# adapter_board.net
KiCad netlist of a schematic drawn in EAGLE
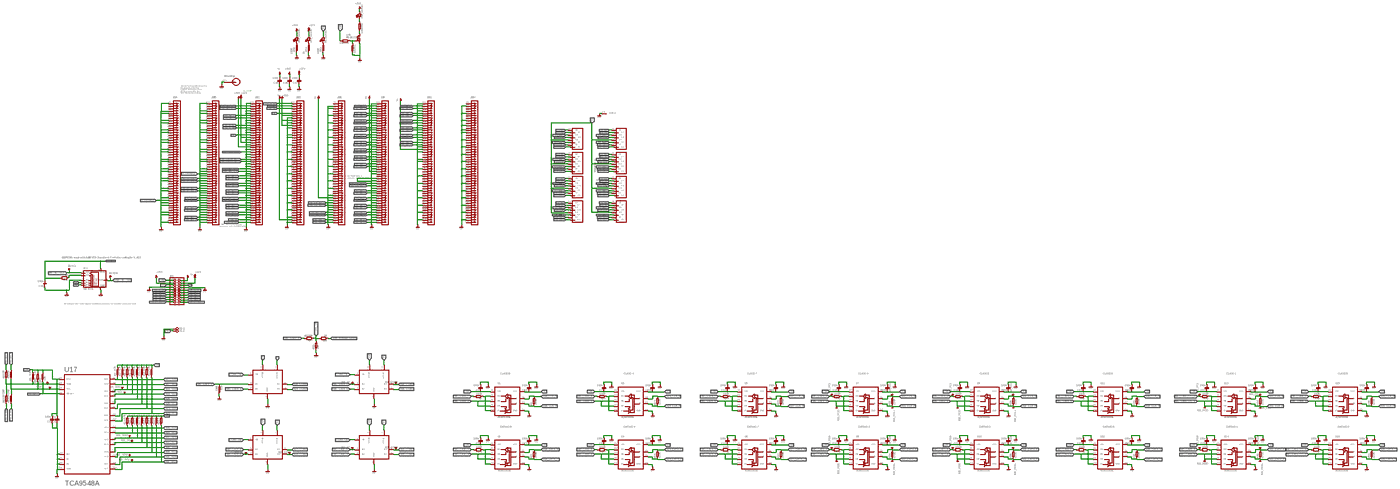
[diagram p0: schematic, sheet 1, overview]
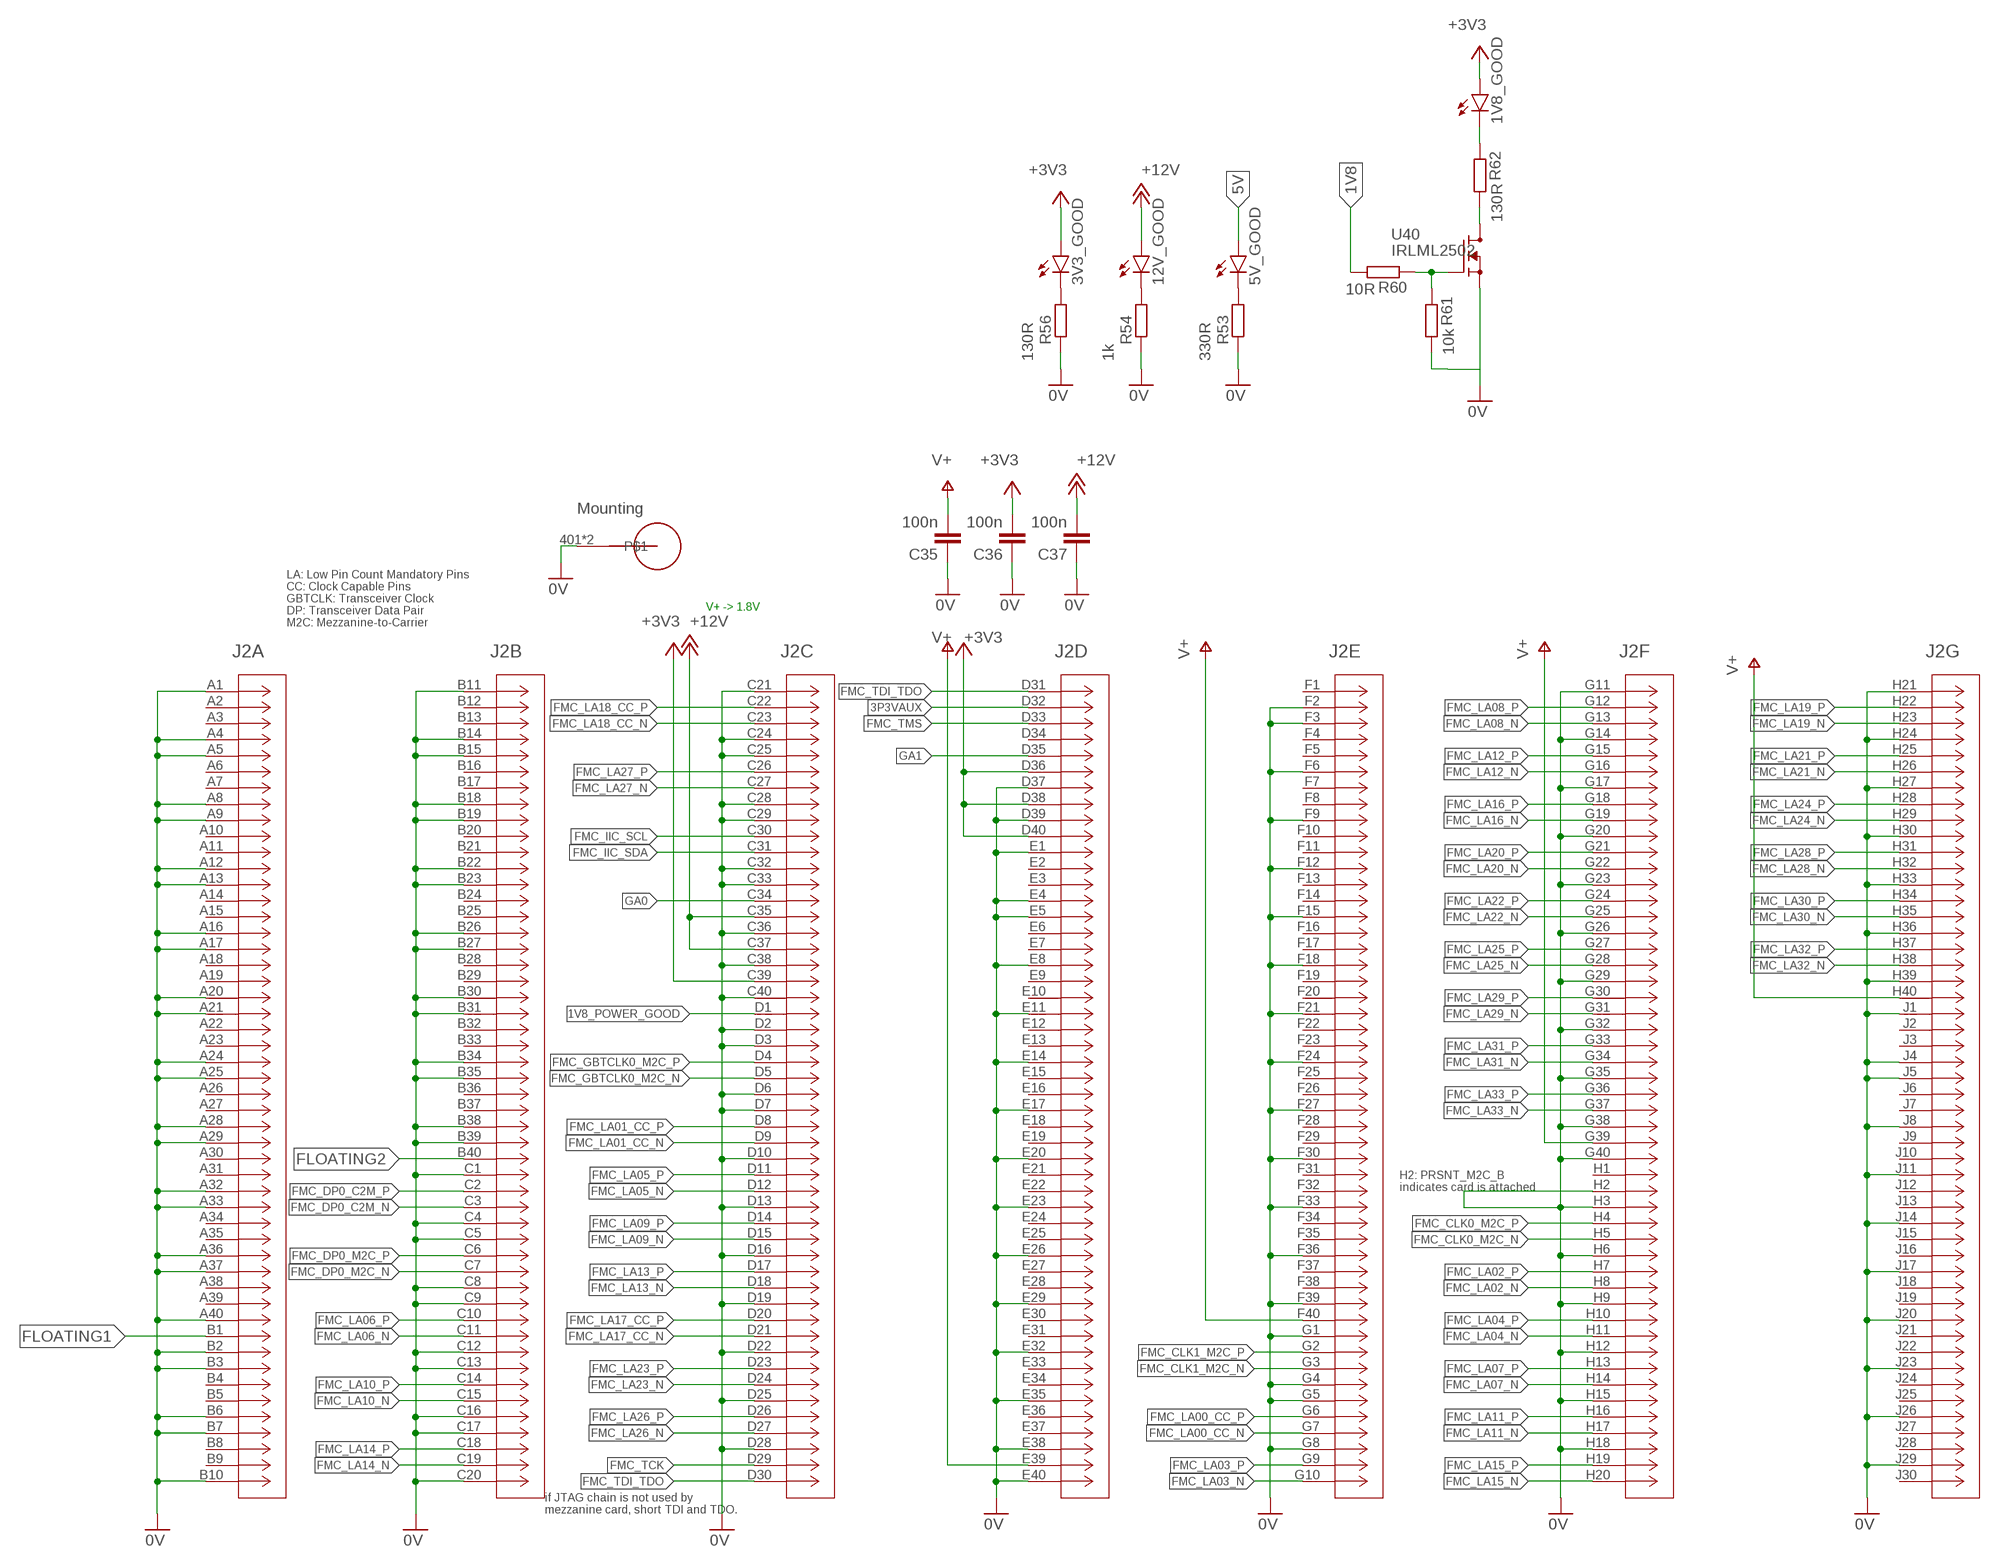
[diagram p1: schematic, sheet 1, part 1 of 5]
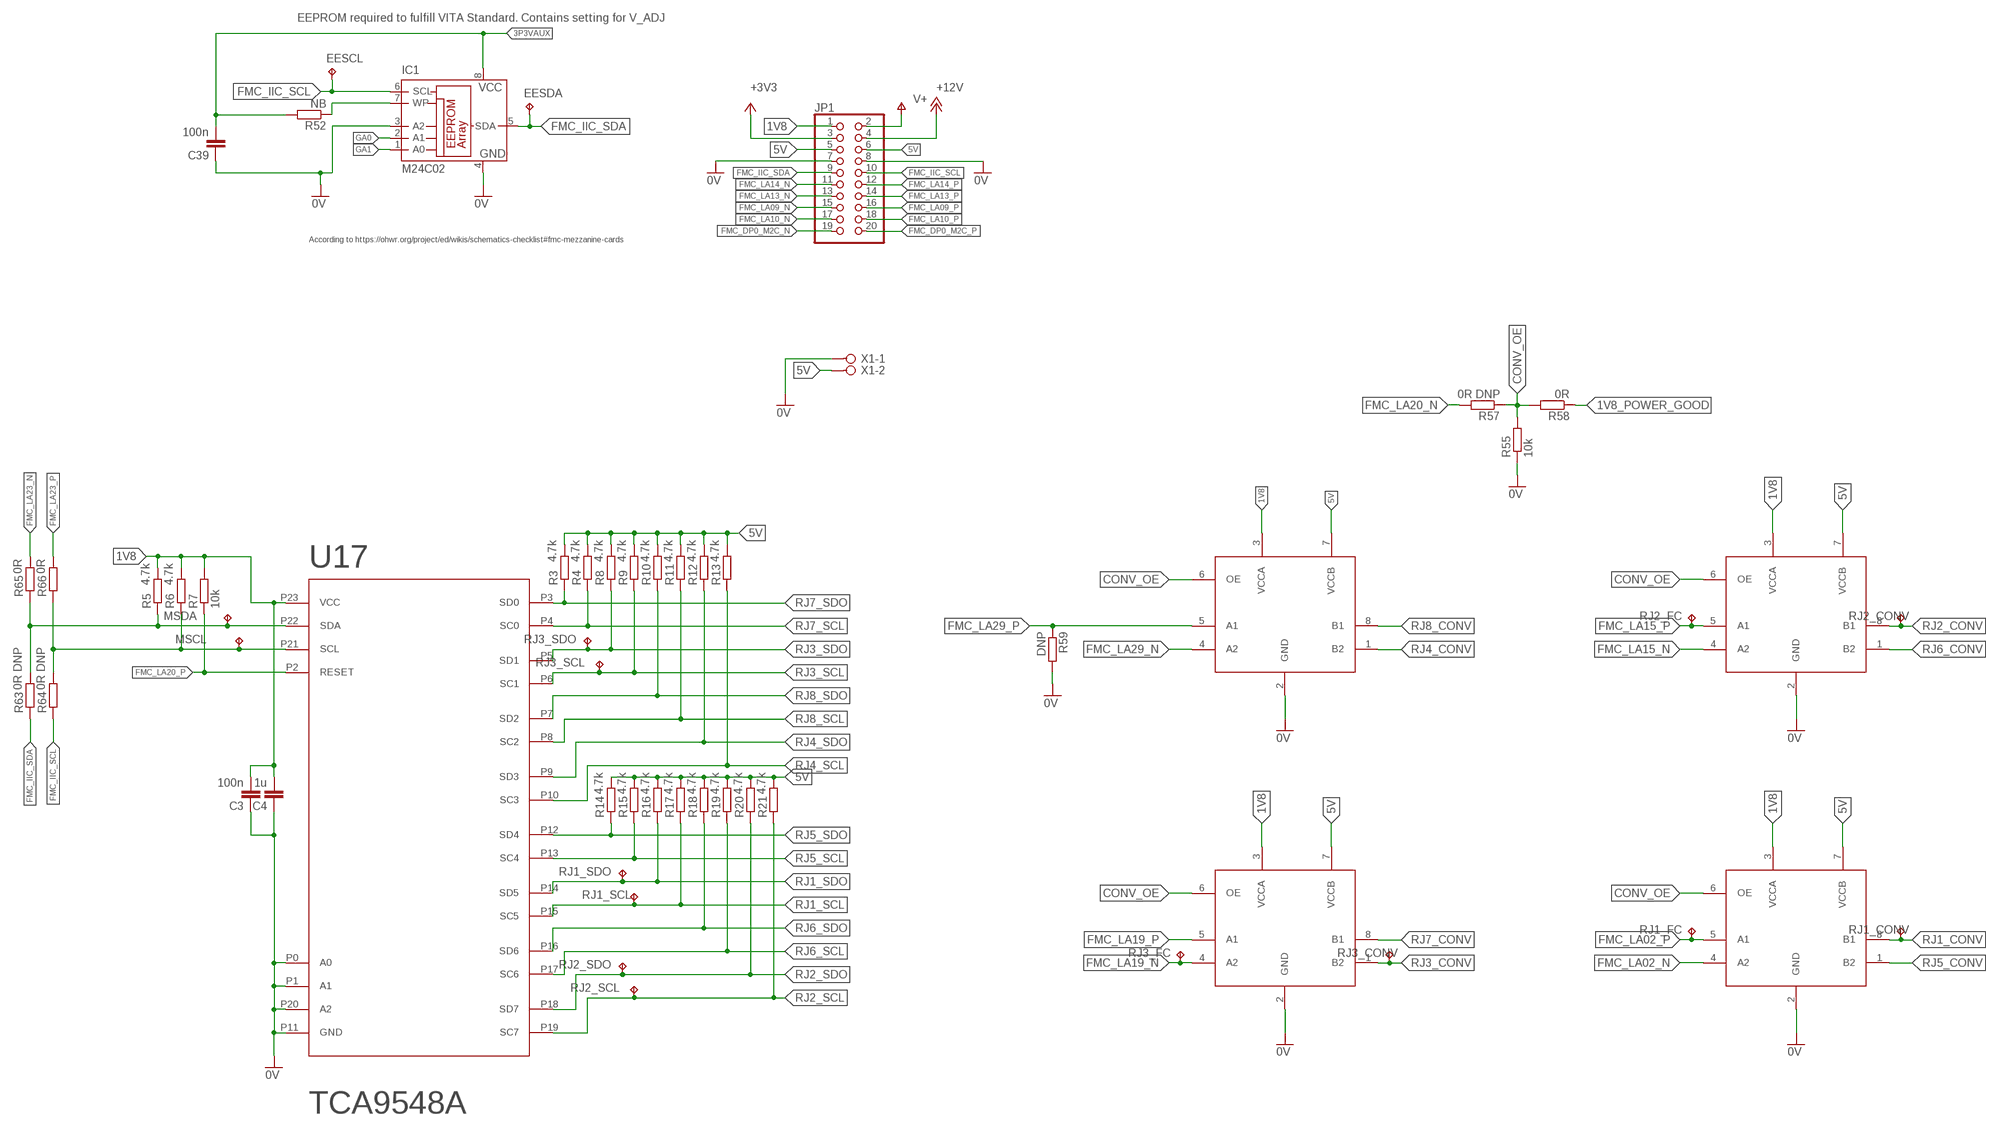
[diagram p2: schematic, sheet 1, part 2 of 5]
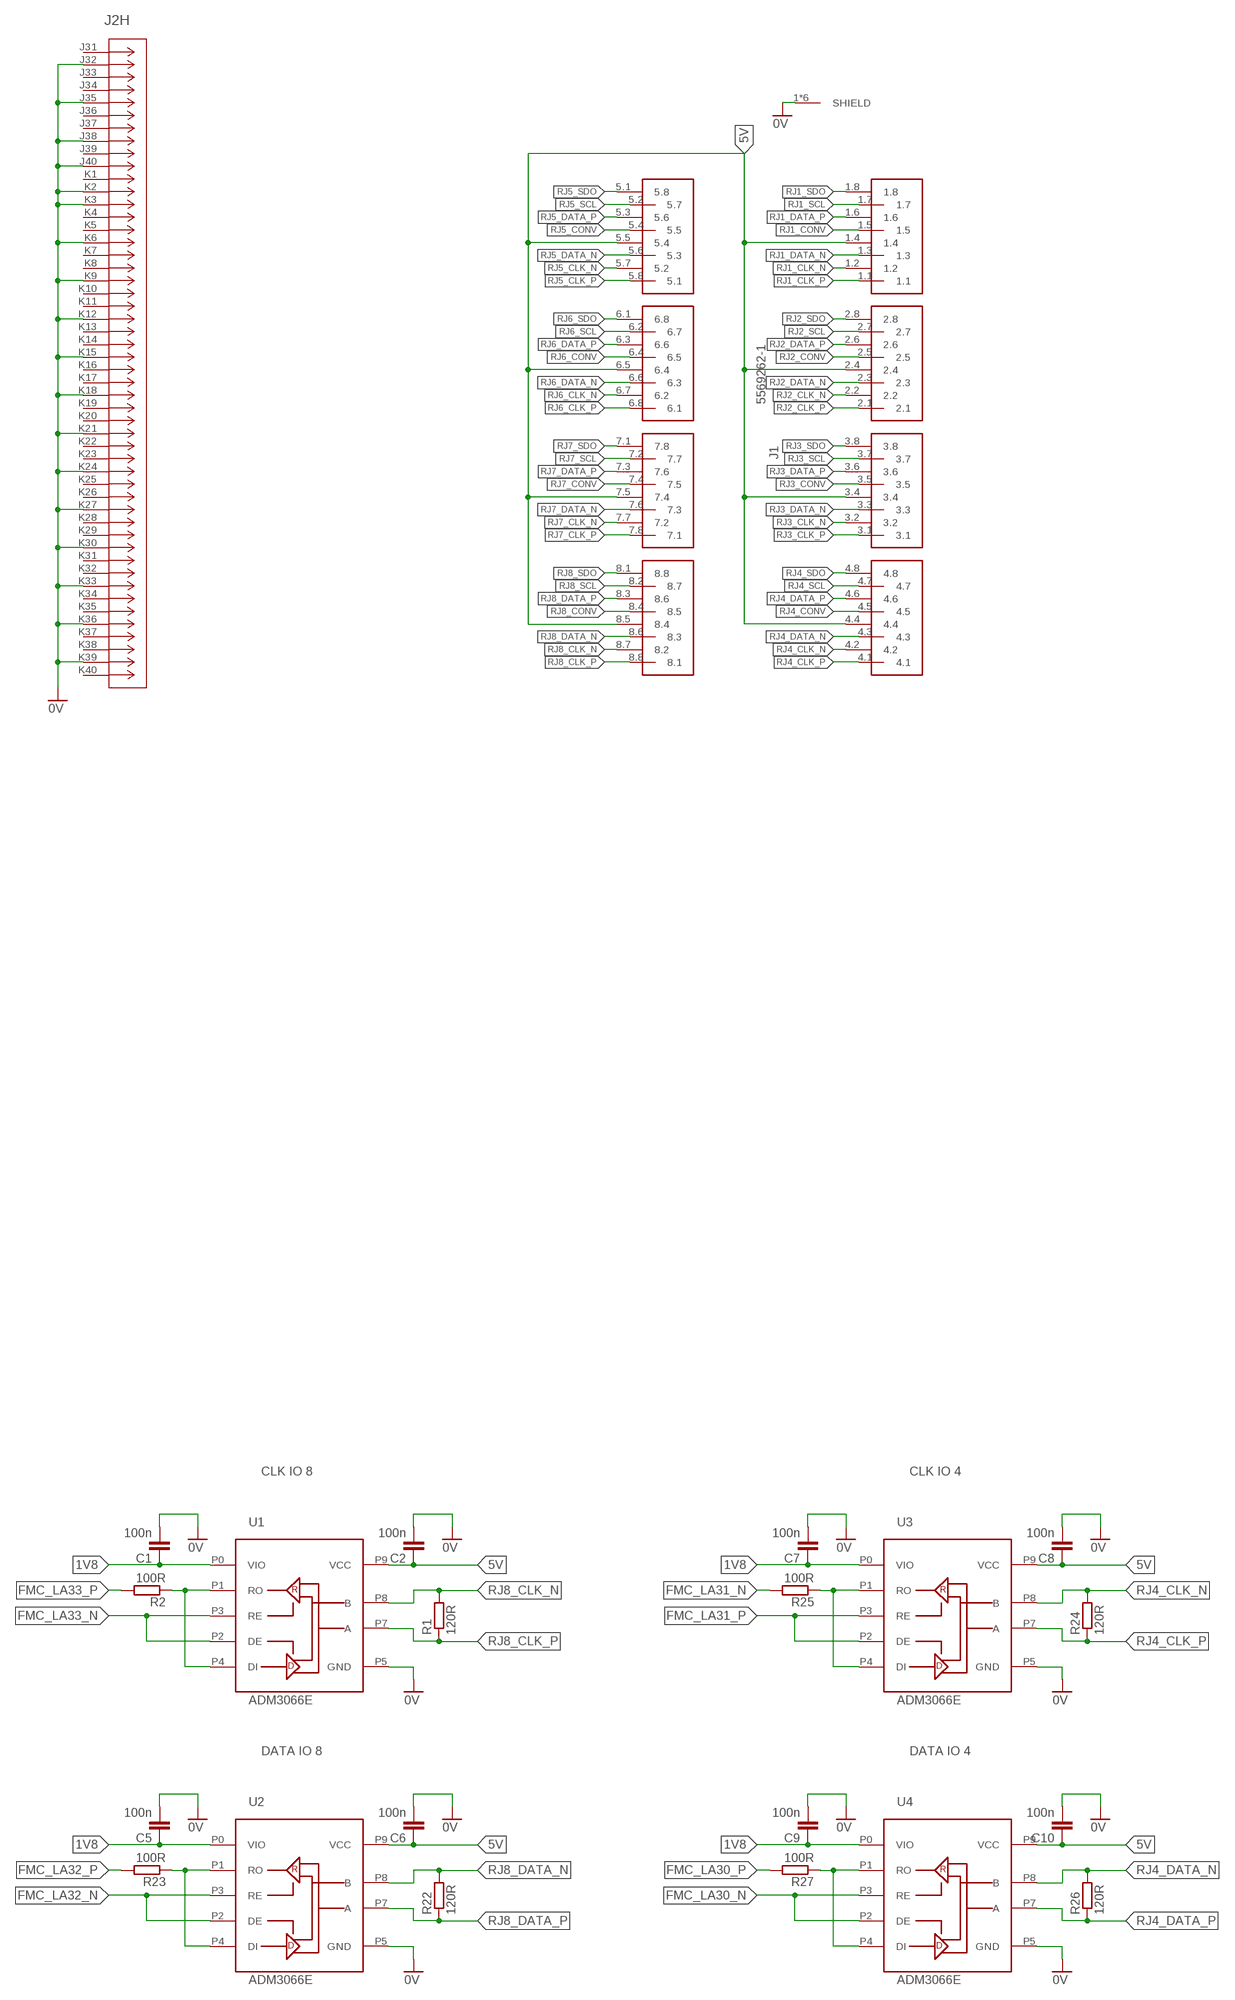
[diagram p3: schematic, sheet 1, part 3 of 5]
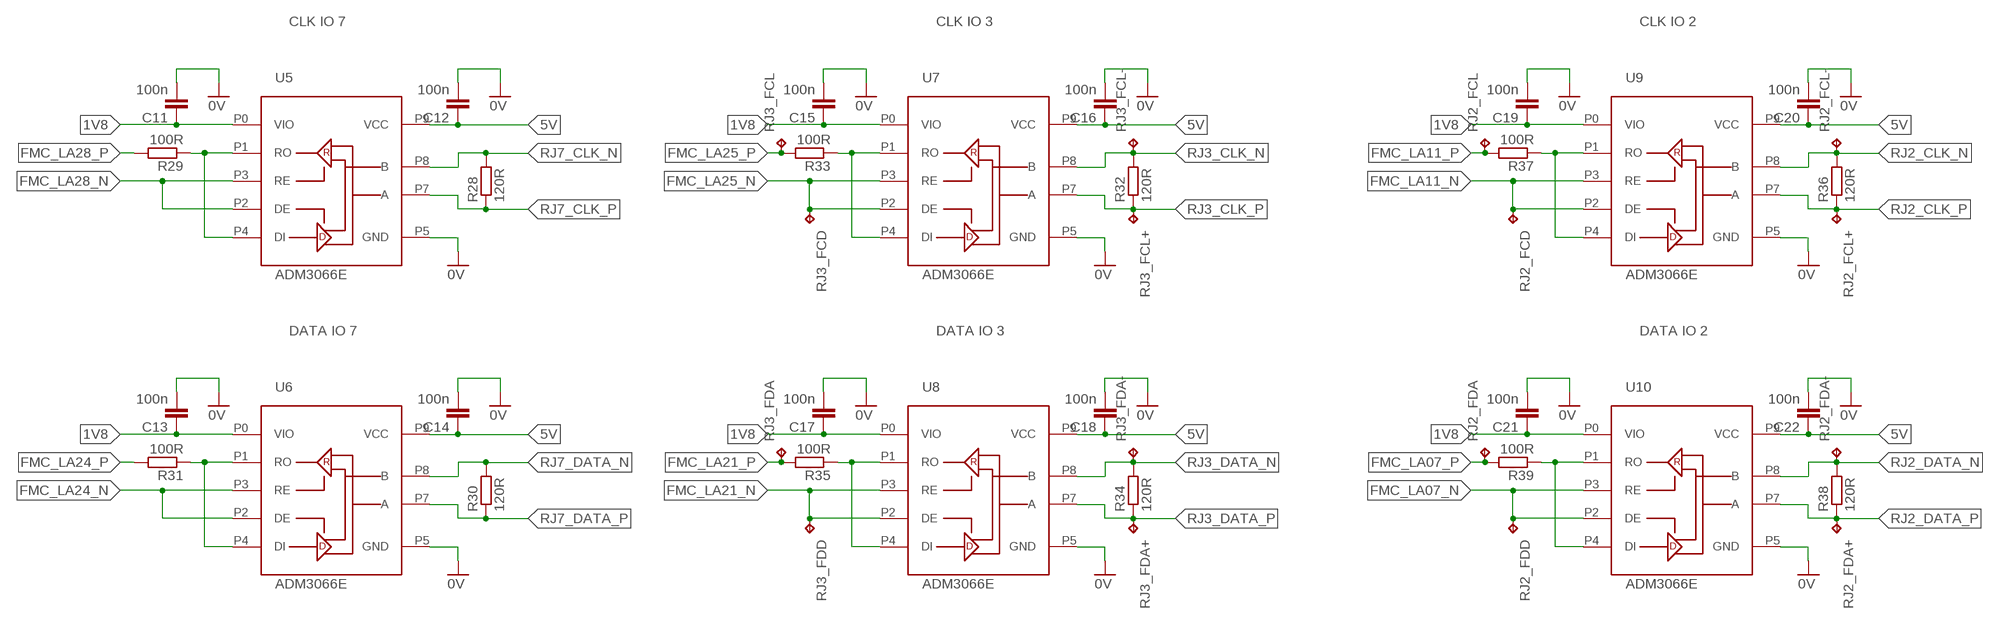
[diagram p4: schematic, sheet 1, part 4 of 5]
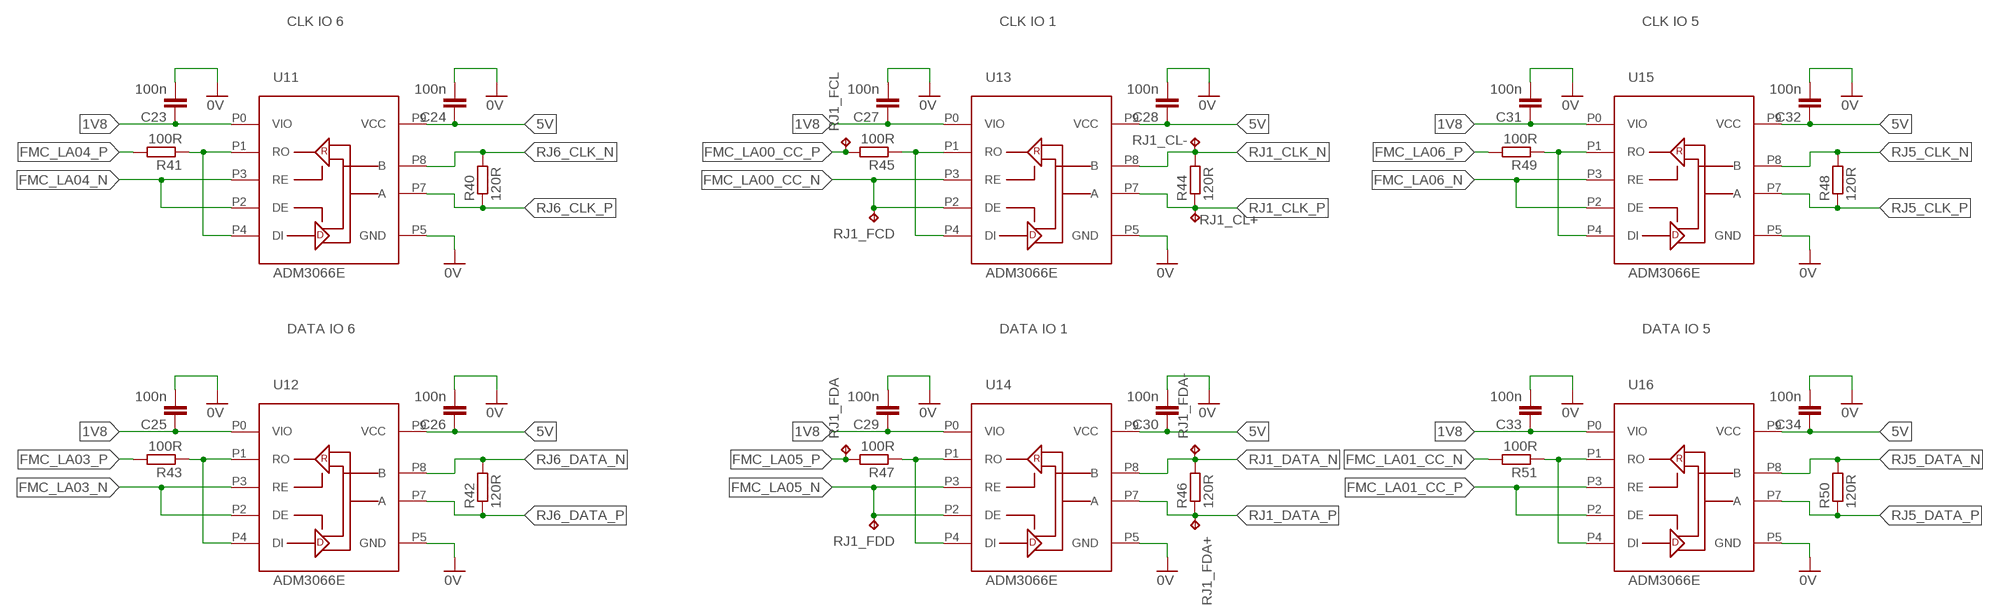
[diagram p5: schematic, sheet 1, part 5 of 5]

(export (version "E")
  (design (tool "Eeschema 10.0.6"))
  (components
    (comp (ref "1V8_GOOD")
      (value "LEDCHIPLED_0805")
      (footprint "eagle-import:CHIPLED_0805")
      (libsource (lib "eagle-import") (part "LEDCHIPLED_0805"))
    )
    (comp (ref "3V3_GOOD")
      (value "LEDCHIPLED_0805")
      (footprint "eagle-import:CHIPLED_0805")
      (libsource (lib "eagle-import") (part "LEDCHIPLED_0805"))
    )
    (comp (ref "5V_GOOD")
      (value "LEDCHIPLED_0805")
      (footprint "eagle-import:CHIPLED_0805")
      (libsource (lib "eagle-import") (part "LEDCHIPLED_0805"))
    )
    (comp (ref "12V_GOOD")
      (value "LEDCHIPLED_0805")
      (footprint "eagle-import:CHIPLED_0805")
      (libsource (lib "eagle-import") (part "LEDCHIPLED_0805"))
    )
    (comp (ref "C1")
      (value "100n")
      (footprint "eagle-import:C0603")
      (libsource (lib "eagle-import") (part "C-EUC0603"))
    )
    (comp (ref "C2")
      (value "100n")
      (footprint "eagle-import:C0603")
      (libsource (lib "eagle-import") (part "C-EUC0603"))
    )
    (comp (ref "C3")
      (value "100n")
      (footprint "eagle-import:C0805")
      (libsource (lib "eagle-import") (part "C-EUC0805"))
    )
    (comp (ref "C4")
      (value "1u")
      (footprint "eagle-import:C0805")
      (libsource (lib "eagle-import") (part "C-EUC0805"))
    )
    (comp (ref "C5")
      (value "100n")
      (footprint "eagle-import:C0603")
      (libsource (lib "eagle-import") (part "C-EUC0603"))
    )
    (comp (ref "C6")
      (value "100n")
      (footprint "eagle-import:C0603")
      (libsource (lib "eagle-import") (part "C-EUC0603"))
    )
    (comp (ref "C7")
      (value "100n")
      (footprint "eagle-import:C0603")
      (libsource (lib "eagle-import") (part "C-EUC0603"))
    )
    (comp (ref "C8")
      (value "100n")
      (footprint "eagle-import:C0603")
      (libsource (lib "eagle-import") (part "C-EUC0603"))
    )
    (comp (ref "C9")
      (value "100n")
      (footprint "eagle-import:C0603")
      (libsource (lib "eagle-import") (part "C-EUC0603"))
    )
    (comp (ref "C10")
      (value "100n")
      (footprint "eagle-import:C0603")
      (libsource (lib "eagle-import") (part "C-EUC0603"))
    )
    (comp (ref "C11")
      (value "100n")
      (footprint "eagle-import:C0603")
      (libsource (lib "eagle-import") (part "C-EUC0603"))
    )
    (comp (ref "C12")
      (value "100n")
      (footprint "eagle-import:C0603")
      (libsource (lib "eagle-import") (part "C-EUC0603"))
    )
    (comp (ref "C13")
      (value "100n")
      (footprint "eagle-import:C0603")
      (libsource (lib "eagle-import") (part "C-EUC0603"))
    )
    (comp (ref "C14")
      (value "100n")
      (footprint "eagle-import:C0603")
      (libsource (lib "eagle-import") (part "C-EUC0603"))
    )
    (comp (ref "C15")
      (value "100n")
      (footprint "eagle-import:C0603")
      (libsource (lib "eagle-import") (part "C-EUC0603"))
    )
    (comp (ref "C16")
      (value "100n")
      (footprint "eagle-import:C0603")
      (libsource (lib "eagle-import") (part "C-EUC0603"))
    )
    (comp (ref "C17")
      (value "100n")
      (footprint "eagle-import:C0603")
      (libsource (lib "eagle-import") (part "C-EUC0603"))
    )
    (comp (ref "C18")
      (value "100n")
      (footprint "eagle-import:C0603")
      (libsource (lib "eagle-import") (part "C-EUC0603"))
    )
    (comp (ref "C19")
      (value "100n")
      (footprint "eagle-import:C0603")
      (libsource (lib "eagle-import") (part "C-EUC0603"))
    )
    (comp (ref "C20")
      (value "100n")
      (footprint "eagle-import:C0603")
      (libsource (lib "eagle-import") (part "C-EUC0603"))
    )
    (comp (ref "C21")
      (value "100n")
      (footprint "eagle-import:C0603")
      (libsource (lib "eagle-import") (part "C-EUC0603"))
    )
    (comp (ref "C22")
      (value "100n")
      (footprint "eagle-import:C0603")
      (libsource (lib "eagle-import") (part "C-EUC0603"))
    )
    (comp (ref "C23")
      (value "100n")
      (footprint "eagle-import:C0603")
      (libsource (lib "eagle-import") (part "C-EUC0603"))
    )
    (comp (ref "C24")
      (value "100n")
      (footprint "eagle-import:C0603")
      (libsource (lib "eagle-import") (part "C-EUC0603"))
    )
    (comp (ref "C25")
      (value "100n")
      (footprint "eagle-import:C0603")
      (libsource (lib "eagle-import") (part "C-EUC0603"))
    )
    (comp (ref "C26")
      (value "100n")
      (footprint "eagle-import:C0603")
      (libsource (lib "eagle-import") (part "C-EUC0603"))
    )
    (comp (ref "C27")
      (value "100n")
      (footprint "eagle-import:C0603")
      (libsource (lib "eagle-import") (part "C-EUC0603"))
    )
    (comp (ref "C28")
      (value "100n")
      (footprint "eagle-import:C0603")
      (libsource (lib "eagle-import") (part "C-EUC0603"))
    )
    (comp (ref "C29")
      (value "100n")
      (footprint "eagle-import:C0603")
      (libsource (lib "eagle-import") (part "C-EUC0603"))
    )
    (comp (ref "C30")
      (value "100n")
      (footprint "eagle-import:C0603")
      (libsource (lib "eagle-import") (part "C-EUC0603"))
    )
    (comp (ref "C31")
      (value "100n")
      (footprint "eagle-import:C0603")
      (libsource (lib "eagle-import") (part "C-EUC0603"))
    )
    (comp (ref "C32")
      (value "100n")
      (footprint "eagle-import:C0603")
      (libsource (lib "eagle-import") (part "C-EUC0603"))
    )
    (comp (ref "C33")
      (value "100n")
      (footprint "eagle-import:C0603")
      (libsource (lib "eagle-import") (part "C-EUC0603"))
    )
    (comp (ref "C34")
      (value "100n")
      (footprint "eagle-import:C0603")
      (libsource (lib "eagle-import") (part "C-EUC0603"))
    )
    (comp (ref "C35")
      (value "100n")
      (footprint "eagle-import:C0603")
      (libsource (lib "eagle-import") (part "C-EUC0603"))
    )
    (comp (ref "C36")
      (value "100n")
      (footprint "eagle-import:C0603")
      (libsource (lib "eagle-import") (part "C-EUC0603"))
    )
    (comp (ref "C37")
      (value "100n")
      (footprint "eagle-import:C0603")
      (libsource (lib "eagle-import") (part "C-EUC0603"))
    )
    (comp (ref "C39")
      (value "100n")
      (footprint "eagle-import:C0603")
      (libsource (lib "eagle-import") (part "C-EUC0603"))
    )
    (comp (ref "EESCL")
      (value "TPB1,27")
      (footprint "eagle-import:B1,27")
      (libsource (lib "eagle-import") (part "TPB1,27"))
    )
    (comp (ref "EESDA")
      (value "TPB1,27")
      (footprint "eagle-import:B1,27")
      (libsource (lib "eagle-import") (part "TPB1,27"))
    )
    (comp (ref "IC1")
      (value "M24C02")
      (footprint "eagle-import:TSSOP-8")
      (libsource (lib "eagle-import") (part "N24C02UDTGTSSOP8"))
    )
    (comp (ref "J1")
      (value "5569262-1")
      (footprint "eagle-import:TE_5569262-1")
      (fields (field (name "MF") "TE Connectivity"))
      (libsource (lib "eagle-import") (part "5569262-1"))
    )
    (comp (ref "J2")
      (value "ASP-134488-01")
      (footprint "eagle-import:CONN_ASP-134488-01_SAI")
      (fields
        (field (name "SPICEPREFIX") "X")
        (field (name "COPYRIGHT") "Copyright (C) 2021 Ultra Librarian. All rights reserved.")
      )
      (libsource (lib "eagle-import") (part "ASP-134488-01"))
    )
    (comp (ref "JP1")
      (value "PINHD-2X10")
      (footprint "eagle-import:2X10")
      (libsource (lib "eagle-import") (part "PINHD-2X10"))
    )
    (comp (ref "MSCL")
      (value "TPB1,27")
      (footprint "eagle-import:B1,27")
      (libsource (lib "eagle-import") (part "TPB1,27"))
    )
    (comp (ref "MSDA")
      (value "TPB1,27")
      (footprint "eagle-import:B1,27")
      (libsource (lib "eagle-import") (part "TPB1,27"))
    )
    (comp (ref "R1")
      (value "120R")
      (footprint "eagle-import:R0805")
      (libsource (lib "eagle-import") (part "R-EU_R0805"))
    )
    (comp (ref "R2")
      (value "100R")
      (footprint "eagle-import:R0603")
      (libsource (lib "eagle-import") (part "R-EU_R0603"))
    )
    (comp (ref "R3")
      (value "4.7k")
      (footprint "eagle-import:R0805")
      (libsource (lib "eagle-import") (part "R-EU_R0805"))
    )
    (comp (ref "R4")
      (value "4.7k")
      (footprint "eagle-import:R0805")
      (libsource (lib "eagle-import") (part "R-EU_R0805"))
    )
    (comp (ref "R5")
      (value "4.7k")
      (footprint "eagle-import:R0603")
      (libsource (lib "eagle-import") (part "R-EU_R0603"))
    )
    (comp (ref "R6")
      (value "4.7k")
      (footprint "eagle-import:R0603")
      (libsource (lib "eagle-import") (part "R-EU_R0603"))
    )
    (comp (ref "R7")
      (value "10k")
      (footprint "eagle-import:R0603")
      (libsource (lib "eagle-import") (part "R-EU_R0603"))
    )
    (comp (ref "R8")
      (value "4.7k")
      (footprint "eagle-import:R0805")
      (libsource (lib "eagle-import") (part "R-EU_R0805"))
    )
    (comp (ref "R9")
      (value "4.7k")
      (footprint "eagle-import:R0805")
      (libsource (lib "eagle-import") (part "R-EU_R0805"))
    )
    (comp (ref "R10")
      (value "4.7k")
      (footprint "eagle-import:R0805")
      (libsource (lib "eagle-import") (part "R-EU_R0805"))
    )
    (comp (ref "R11")
      (value "4.7k")
      (footprint "eagle-import:R0805")
      (libsource (lib "eagle-import") (part "R-EU_R0805"))
    )
    (comp (ref "R12")
      (value "4.7k")
      (footprint "eagle-import:R0805")
      (libsource (lib "eagle-import") (part "R-EU_R0805"))
    )
    (comp (ref "R13")
      (value "4.7k")
      (footprint "eagle-import:R0805")
      (libsource (lib "eagle-import") (part "R-EU_R0805"))
    )
    (comp (ref "R14")
      (value "4.7k")
      (footprint "eagle-import:R0805")
      (libsource (lib "eagle-import") (part "R-EU_R0805"))
    )
    (comp (ref "R15")
      (value "4.7k")
      (footprint "eagle-import:R0805")
      (libsource (lib "eagle-import") (part "R-EU_R0805"))
    )
    (comp (ref "R16")
      (value "4.7k")
      (footprint "eagle-import:R0805")
      (libsource (lib "eagle-import") (part "R-EU_R0805"))
    )
    (comp (ref "R17")
      (value "4.7k")
      (footprint "eagle-import:R0805")
      (libsource (lib "eagle-import") (part "R-EU_R0805"))
    )
    (comp (ref "R18")
      (value "4.7k")
      (footprint "eagle-import:R0805")
      (libsource (lib "eagle-import") (part "R-EU_R0805"))
    )
    (comp (ref "R19")
      (value "4.7k")
      (footprint "eagle-import:R0805")
      (libsource (lib "eagle-import") (part "R-EU_R0805"))
    )
    (comp (ref "R20")
      (value "4.7k")
      (footprint "eagle-import:R0805")
      (libsource (lib "eagle-import") (part "R-EU_R0805"))
    )
    (comp (ref "R21")
      (value "4.7k")
      (footprint "eagle-import:R0805")
      (libsource (lib "eagle-import") (part "R-EU_R0805"))
    )
    (comp (ref "R22")
      (value "120R")
      (footprint "eagle-import:R0805")
      (libsource (lib "eagle-import") (part "R-EU_R0805"))
    )
    (comp (ref "R23")
      (value "100R")
      (footprint "eagle-import:R0603")
      (libsource (lib "eagle-import") (part "R-EU_R0603"))
    )
    (comp (ref "R24")
      (value "120R")
      (footprint "eagle-import:R0805")
      (libsource (lib "eagle-import") (part "R-EU_R0805"))
    )
    (comp (ref "R25")
      (value "100R")
      (footprint "eagle-import:R0603")
      (libsource (lib "eagle-import") (part "R-EU_R0603"))
    )
    (comp (ref "R26")
      (value "120R")
      (footprint "eagle-import:R0805")
      (libsource (lib "eagle-import") (part "R-EU_R0805"))
    )
    (comp (ref "R27")
      (value "100R")
      (footprint "eagle-import:R0603")
      (libsource (lib "eagle-import") (part "R-EU_R0603"))
    )
    (comp (ref "R28")
      (value "120R")
      (footprint "eagle-import:R0805")
      (libsource (lib "eagle-import") (part "R-EU_R0805"))
    )
    (comp (ref "R29")
      (value "100R")
      (footprint "eagle-import:R0603")
      (libsource (lib "eagle-import") (part "R-EU_R0603"))
    )
    (comp (ref "R30")
      (value "120R")
      (footprint "eagle-import:R0805")
      (libsource (lib "eagle-import") (part "R-EU_R0805"))
    )
    (comp (ref "R31")
      (value "100R")
      (footprint "eagle-import:R0603")
      (libsource (lib "eagle-import") (part "R-EU_R0603"))
    )
    (comp (ref "R32")
      (value "120R")
      (footprint "eagle-import:R0805")
      (libsource (lib "eagle-import") (part "R-EU_R0805"))
    )
    (comp (ref "R33")
      (value "100R")
      (footprint "eagle-import:R0603")
      (libsource (lib "eagle-import") (part "R-EU_R0603"))
    )
    (comp (ref "R34")
      (value "120R")
      (footprint "eagle-import:R0805")
      (libsource (lib "eagle-import") (part "R-EU_R0805"))
    )
    (comp (ref "R35")
      (value "100R")
      (footprint "eagle-import:R0603")
      (libsource (lib "eagle-import") (part "R-EU_R0603"))
    )
    (comp (ref "R36")
      (value "120R")
      (footprint "eagle-import:R0805")
      (libsource (lib "eagle-import") (part "R-EU_R0805"))
    )
    (comp (ref "R37")
      (value "100R")
      (footprint "eagle-import:R0603")
      (libsource (lib "eagle-import") (part "R-EU_R0603"))
    )
    (comp (ref "R38")
      (value "120R")
      (footprint "eagle-import:R0805")
      (libsource (lib "eagle-import") (part "R-EU_R0805"))
    )
    (comp (ref "R39")
      (value "100R")
      (footprint "eagle-import:R0603")
      (libsource (lib "eagle-import") (part "R-EU_R0603"))
    )
    (comp (ref "R40")
      (value "120R")
      (footprint "eagle-import:R0805")
      (libsource (lib "eagle-import") (part "R-EU_R0805"))
    )
    (comp (ref "R41")
      (value "100R")
      (footprint "eagle-import:R0603")
      (libsource (lib "eagle-import") (part "R-EU_R0603"))
    )
    (comp (ref "R42")
      (value "120R")
      (footprint "eagle-import:R0805")
      (libsource (lib "eagle-import") (part "R-EU_R0805"))
    )
    (comp (ref "R43")
      (value "100R")
      (footprint "eagle-import:R0603")
      (libsource (lib "eagle-import") (part "R-EU_R0603"))
    )
    (comp (ref "R44")
      (value "120R")
      (footprint "eagle-import:R0805")
      (libsource (lib "eagle-import") (part "R-EU_R0805"))
    )
    (comp (ref "R45")
      (value "100R")
      (footprint "eagle-import:R0603")
      (libsource (lib "eagle-import") (part "R-EU_R0603"))
    )
    (comp (ref "R46")
      (value "120R")
      (footprint "eagle-import:R0805")
      (libsource (lib "eagle-import") (part "R-EU_R0805"))
    )
    (comp (ref "R47")
      (value "100R")
      (footprint "eagle-import:R0603")
      (libsource (lib "eagle-import") (part "R-EU_R0603"))
    )
    (comp (ref "R48")
      (value "120R")
      (footprint "eagle-import:R0805")
      (libsource (lib "eagle-import") (part "R-EU_R0805"))
    )
    (comp (ref "R49")
      (value "100R")
      (footprint "eagle-import:R0603")
      (libsource (lib "eagle-import") (part "R-EU_R0603"))
    )
    (comp (ref "R50")
      (value "120R")
      (footprint "eagle-import:R0805")
      (libsource (lib "eagle-import") (part "R-EU_R0805"))
    )
    (comp (ref "R51")
      (value "100R")
      (footprint "eagle-import:R0603")
      (libsource (lib "eagle-import") (part "R-EU_R0603"))
    )
    (comp (ref "R52")
      (value "NB")
      (footprint "eagle-import:R0603")
      (libsource (lib "eagle-import") (part "R-EU_R0603"))
    )
    (comp (ref "R53")
      (value "330R")
      (footprint "eagle-import:R0805")
      (libsource (lib "eagle-import") (part "resistor_348_R-EU_R0805"))
    )
    (comp (ref "R54")
      (value "1k")
      (footprint "eagle-import:R0805")
      (libsource (lib "eagle-import") (part "resistor_348_R-EU_R0805"))
    )
    (comp (ref "R55")
      (value "10k")
      (footprint "eagle-import:R0603")
      (libsource (lib "eagle-import") (part "R-EU_R0603"))
    )
    (comp (ref "R56")
      (value "130R")
      (footprint "eagle-import:R0805")
      (libsource (lib "eagle-import") (part "resistor_348_R-EU_R0805"))
    )
    (comp (ref "R57")
      (value "0R DNP")
      (footprint "eagle-import:R0603")
      (libsource (lib "eagle-import") (part "R-EU_R0603"))
    )
    (comp (ref "R58")
      (value "0R")
      (footprint "eagle-import:R0603")
      (libsource (lib "eagle-import") (part "R-EU_R0603"))
    )
    (comp (ref "R59")
      (value "DNP")
      (footprint "eagle-import:R0805")
      (libsource (lib "eagle-import") (part "R-EU_R0805"))
    )
    (comp (ref "R60")
      (value "10R")
      (footprint "eagle-import:R0603")
      (libsource (lib "eagle-import") (part "resistor_348_R-EU_R0603"))
    )
    (comp (ref "R61")
      (value "10k")
      (footprint "eagle-import:R0603")
      (libsource (lib "eagle-import") (part "resistor_348_R-EU_R0603"))
    )
    (comp (ref "R62")
      (value "130R")
      (footprint "eagle-import:R0805")
      (libsource (lib "eagle-import") (part "resistor_348_R-EU_R0805"))
    )
    (comp (ref "R63")
      (value "0R DNP")
      (footprint "eagle-import:R0805")
      (libsource (lib "eagle-import") (part "R-EU_R0805"))
    )
    (comp (ref "R64")
      (value "0R DNP")
      (footprint "eagle-import:R0805")
      (libsource (lib "eagle-import") (part "R-EU_R0805"))
    )
    (comp (ref "R65")
      (value "0R")
      (footprint "eagle-import:R0805")
      (libsource (lib "eagle-import") (part "R-EU_R0805"))
    )
    (comp (ref "R66")
      (value "0R")
      (footprint "eagle-import:R0805")
      (libsource (lib "eagle-import") (part "R-EU_R0805"))
    )
    (comp (ref "RJ1_CL+")
      (value "TPB1,27")
      (footprint "eagle-import:B1,27")
      (libsource (lib "eagle-import") (part "TPB1,27"))
    )
    (comp (ref "RJ1_CL-")
      (value "TPB1,27")
      (footprint "eagle-import:B1,27")
      (libsource (lib "eagle-import") (part "TPB1,27"))
    )
    (comp (ref "RJ1_CONV")
      (value "TPB1,27")
      (footprint "eagle-import:B1,27")
      (libsource (lib "eagle-import") (part "TPB1,27"))
    )
    (comp (ref "RJ1_FC")
      (value "TPB1,27")
      (footprint "eagle-import:B1,27")
      (libsource (lib "eagle-import") (part "TPB1,27"))
    )
    (comp (ref "RJ1_FCD")
      (value "TPB1,27")
      (footprint "eagle-import:B1,27")
      (libsource (lib "eagle-import") (part "TPB1,27"))
    )
    (comp (ref "RJ1_FCL")
      (value "TPB1,27")
      (footprint "eagle-import:B1,27")
      (libsource (lib "eagle-import") (part "TPB1,27"))
    )
    (comp (ref "RJ1_FDA")
      (value "TPB1,27")
      (footprint "eagle-import:B1,27")
      (libsource (lib "eagle-import") (part "TPB1,27"))
    )
    (comp (ref "RJ1_FDA+")
      (value "TPB1,27")
      (footprint "eagle-import:B1,27")
      (libsource (lib "eagle-import") (part "TPB1,27"))
    )
    (comp (ref "RJ1_FDA-")
      (value "TPB1,27")
      (footprint "eagle-import:B1,27")
      (libsource (lib "eagle-import") (part "TPB1,27"))
    )
    (comp (ref "RJ1_FDD")
      (value "TPB1,27")
      (footprint "eagle-import:B1,27")
      (libsource (lib "eagle-import") (part "TPB1,27"))
    )
    (comp (ref "RJ1_SCL")
      (value "TPB1,27")
      (footprint "eagle-import:B1,27")
      (libsource (lib "eagle-import") (part "TPB1,27"))
    )
    (comp (ref "RJ1_SDO")
      (value "TPB1,27")
      (footprint "eagle-import:B1,27")
      (libsource (lib "eagle-import") (part "TPB1,27"))
    )
    (comp (ref "RJ2_CONV")
      (value "TPB1,27")
      (footprint "eagle-import:B1,27")
      (libsource (lib "eagle-import") (part "TPB1,27"))
    )
    (comp (ref "RJ2_FC")
      (value "TPB1,27")
      (footprint "eagle-import:B1,27")
      (libsource (lib "eagle-import") (part "TPB1,27"))
    )
    (comp (ref "RJ2_FCD")
      (value "TPB1,27")
      (footprint "eagle-import:B1,27")
      (libsource (lib "eagle-import") (part "TPB1,27"))
    )
    (comp (ref "RJ2_FCL")
      (value "TPB1,27")
      (footprint "eagle-import:B1,27")
      (libsource (lib "eagle-import") (part "TPB1,27"))
    )
    (comp (ref "RJ2_FCL+")
      (value "TPB1,27")
      (footprint "eagle-import:B1,27")
      (libsource (lib "eagle-import") (part "TPB1,27"))
    )
    (comp (ref "RJ2_FCL-")
      (value "TPB1,27")
      (footprint "eagle-import:B1,27")
      (libsource (lib "eagle-import") (part "TPB1,27"))
    )
    (comp (ref "RJ2_FDA")
      (value "TPB1,27")
      (footprint "eagle-import:B1,27")
      (libsource (lib "eagle-import") (part "TPB1,27"))
    )
    (comp (ref "RJ2_FDA+")
      (value "TPB1,27")
      (footprint "eagle-import:B1,27")
      (libsource (lib "eagle-import") (part "TPB1,27"))
    )
    (comp (ref "RJ2_FDA-")
      (value "TPB1,27")
      (footprint "eagle-import:B1,27")
      (libsource (lib "eagle-import") (part "TPB1,27"))
    )
    (comp (ref "RJ2_FDD")
      (value "TPB1,27")
      (footprint "eagle-import:B1,27")
      (libsource (lib "eagle-import") (part "TPB1,27"))
    )
    (comp (ref "RJ2_SCL")
      (value "TPB1,27")
      (footprint "eagle-import:B1,27")
      (libsource (lib "eagle-import") (part "TPB1,27"))
    )
    (comp (ref "RJ2_SDO")
      (value "TPB1,27")
      (footprint "eagle-import:B1,27")
      (libsource (lib "eagle-import") (part "TPB1,27"))
    )
    (comp (ref "RJ3_CONV")
      (value "TPB1,27")
      (footprint "eagle-import:B1,27")
      (libsource (lib "eagle-import") (part "TPB1,27"))
    )
    (comp (ref "RJ3_FC")
      (value "TPB1,27")
      (footprint "eagle-import:B1,27")
      (libsource (lib "eagle-import") (part "TPB1,27"))
    )
    (comp (ref "RJ3_FCD")
      (value "TPB1,27")
      (footprint "eagle-import:B1,27")
      (libsource (lib "eagle-import") (part "TPB1,27"))
    )
    (comp (ref "RJ3_FCL")
      (value "TPB1,27")
      (footprint "eagle-import:B1,27")
      (libsource (lib "eagle-import") (part "TPB1,27"))
    )
    (comp (ref "RJ3_FCL+")
      (value "TPB1,27")
      (footprint "eagle-import:B1,27")
      (libsource (lib "eagle-import") (part "TPB1,27"))
    )
    (comp (ref "RJ3_FCL-")
      (value "TPB1,27")
      (footprint "eagle-import:B1,27")
      (libsource (lib "eagle-import") (part "TPB1,27"))
    )
    (comp (ref "RJ3_FDA")
      (value "TPB1,27")
      (footprint "eagle-import:B1,27")
      (libsource (lib "eagle-import") (part "TPB1,27"))
    )
    (comp (ref "RJ3_FDA+")
      (value "TPB1,27")
      (footprint "eagle-import:B1,27")
      (libsource (lib "eagle-import") (part "TPB1,27"))
    )
    (comp (ref "RJ3_FDA-")
      (value "TPB1,27")
      (footprint "eagle-import:B1,27")
      (libsource (lib "eagle-import") (part "TPB1,27"))
    )
    (comp (ref "RJ3_FDD")
      (value "TPB1,27")
      (footprint "eagle-import:B1,27")
      (libsource (lib "eagle-import") (part "TPB1,27"))
    )
    (comp (ref "RJ3_SCL")
      (value "TPB1,27")
      (footprint "eagle-import:B1,27")
      (libsource (lib "eagle-import") (part "TPB1,27"))
    )
    (comp (ref "RJ3_SDO")
      (value "TPB1,27")
      (footprint "eagle-import:B1,27")
      (libsource (lib "eagle-import") (part "TPB1,27"))
    )
    (comp (ref "U1")
      (value "ADM3066E")
      (footprint "eagle-import:MSOP-10")
      (libsource (lib "eagle-import") (part "ADM3066E"))
    )
    (comp (ref "U2")
      (value "ADM3066E")
      (footprint "eagle-import:MSOP-10")
      (libsource (lib "eagle-import") (part "ADM3066E"))
    )
    (comp (ref "U3")
      (value "ADM3066E")
      (footprint "eagle-import:MSOP-10")
      (libsource (lib "eagle-import") (part "ADM3066E"))
    )
    (comp (ref "U4")
      (value "ADM3066E")
      (footprint "eagle-import:MSOP-10")
      (libsource (lib "eagle-import") (part "ADM3066E"))
    )
    (comp (ref "U5")
      (value "ADM3066E")
      (footprint "eagle-import:MSOP-10")
      (libsource (lib "eagle-import") (part "ADM3066E"))
    )
    (comp (ref "U6")
      (value "ADM3066E")
      (footprint "eagle-import:MSOP-10")
      (libsource (lib "eagle-import") (part "ADM3066E"))
    )
    (comp (ref "U7")
      (value "ADM3066E")
      (footprint "eagle-import:MSOP-10")
      (libsource (lib "eagle-import") (part "ADM3066E"))
    )
    (comp (ref "U8")
      (value "ADM3066E")
      (footprint "eagle-import:MSOP-10")
      (libsource (lib "eagle-import") (part "ADM3066E"))
    )
    (comp (ref "U9")
      (value "ADM3066E")
      (footprint "eagle-import:MSOP-10")
      (libsource (lib "eagle-import") (part "ADM3066E"))
    )
    (comp (ref "U10")
      (value "ADM3066E")
      (footprint "eagle-import:MSOP-10")
      (libsource (lib "eagle-import") (part "ADM3066E"))
    )
    (comp (ref "U11")
      (value "ADM3066E")
      (footprint "eagle-import:MSOP-10")
      (libsource (lib "eagle-import") (part "ADM3066E"))
    )
    (comp (ref "U12")
      (value "ADM3066E")
      (footprint "eagle-import:MSOP-10")
      (libsource (lib "eagle-import") (part "ADM3066E"))
    )
    (comp (ref "U13")
      (value "ADM3066E")
      (footprint "eagle-import:MSOP-10")
      (libsource (lib "eagle-import") (part "ADM3066E"))
    )
    (comp (ref "U14")
      (value "ADM3066E")
      (footprint "eagle-import:MSOP-10")
      (libsource (lib "eagle-import") (part "ADM3066E"))
    )
    (comp (ref "U15")
      (value "ADM3066E")
      (footprint "eagle-import:MSOP-10")
      (libsource (lib "eagle-import") (part "ADM3066E"))
    )
    (comp (ref "U16")
      (value "ADM3066E")
      (footprint "eagle-import:MSOP-10")
      (libsource (lib "eagle-import") (part "ADM3066E"))
    )
    (comp (ref "U17")
      (value "TCA9548A")
      (footprint "eagle-import:PCA9548")
      (libsource (lib "eagle-import") (part "PCA9548A"))
    )
    (comp (ref "U18")
      (value "TXS0102")
      (footprint "eagle-import:VSSOP-8")
      (libsource (lib "eagle-import") (part "TXS0102"))
    )
    (comp (ref "U19")
      (value "TXS0102")
      (footprint "eagle-import:VSSOP-8")
      (libsource (lib "eagle-import") (part "TXS0102"))
    )
    (comp (ref "U20")
      (value "TXS0102")
      (footprint "eagle-import:VSSOP-8")
      (libsource (lib "eagle-import") (part "TXS0102"))
    )
    (comp (ref "U21")
      (value "TXS0102")
      (footprint "eagle-import:VSSOP-8")
      (libsource (lib "eagle-import") (part "TXS0102"))
    )
    (comp (ref "U40")
      (value "IRLML2502")
      (footprint "eagle-import:SOT23-IRLML")
      (libsource (lib "eagle-import") (part "IRLML2502"))
    )
    (comp (ref "X1")
      (value "W237-02P")
      (footprint "eagle-import:W237-132")
      (libsource (lib "eagle-import") (part "W237-02P"))
    )
  )
  (nets
    (net (code "1") (name "+3V3") (class "Default")
      (node (ref "1V8_GOOD") (pin "A") (pinfunction "A_A") (pintype "passive"))
      (node (ref "3V3_GOOD") (pin "A") (pinfunction "A_A") (pintype "passive"))
      (node (ref "C36") (pin "2") (pinfunction "2_2") (pintype "passive"))
      (node (ref "J2") (pin "C39") (pinfunction "C39_C39") (pintype "passive"))
      (node (ref "J2") (pin "D36") (pinfunction "D36_D36") (pintype "passive"))
      (node (ref "J2") (pin "D38") (pinfunction "D38_D38") (pintype "passive"))
      (node (ref "J2") (pin "D40") (pinfunction "D40_D40") (pintype "passive"))
      (node (ref "JP1") (pin "3") (pinfunction "3_3") (pintype "passive"))
    )
    (net (code "2") (name "+12V") (class "Default")
      (node (ref "12V_GOOD") (pin "A") (pinfunction "A_A") (pintype "passive"))
      (node (ref "C37") (pin "2") (pinfunction "2_2") (pintype "passive"))
      (node (ref "J2") (pin "C35") (pinfunction "C35_C35") (pintype "passive"))
      (node (ref "J2") (pin "C37") (pinfunction "C37_C37") (pintype "passive"))
      (node (ref "JP1") (pin "4") (pinfunction "4_4") (pintype "passive"))
    )
    (net (code "3") (name "0V") (class "Default")
      (node (ref "C1") (pin "2") (pinfunction "2_2") (pintype "passive"))
      (node (ref "C10") (pin "2") (pinfunction "2_2") (pintype "passive"))
      (node (ref "C11") (pin "2") (pinfunction "2_2") (pintype "passive"))
      (node (ref "C12") (pin "2") (pinfunction "2_2") (pintype "passive"))
      (node (ref "C13") (pin "2") (pinfunction "2_2") (pintype "passive"))
      (node (ref "C14") (pin "2") (pinfunction "2_2") (pintype "passive"))
      (node (ref "C15") (pin "2") (pinfunction "2_2") (pintype "passive"))
      (node (ref "C16") (pin "2") (pinfunction "2_2") (pintype "passive"))
      (node (ref "C17") (pin "2") (pinfunction "2_2") (pintype "passive"))
      (node (ref "C18") (pin "2") (pinfunction "2_2") (pintype "passive"))
      (node (ref "C19") (pin "2") (pinfunction "2_2") (pintype "passive"))
      (node (ref "C2") (pin "2") (pinfunction "2_2") (pintype "passive"))
      (node (ref "C20") (pin "2") (pinfunction "2_2") (pintype "passive"))
      (node (ref "C21") (pin "2") (pinfunction "2_2") (pintype "passive"))
      (node (ref "C22") (pin "2") (pinfunction "2_2") (pintype "passive"))
      (node (ref "C23") (pin "2") (pinfunction "2_2") (pintype "passive"))
      (node (ref "C24") (pin "2") (pinfunction "2_2") (pintype "passive"))
      (node (ref "C25") (pin "2") (pinfunction "2_2") (pintype "passive"))
      (node (ref "C26") (pin "2") (pinfunction "2_2") (pintype "passive"))
      (node (ref "C27") (pin "2") (pinfunction "2_2") (pintype "passive"))
      (node (ref "C28") (pin "2") (pinfunction "2_2") (pintype "passive"))
      (node (ref "C29") (pin "2") (pinfunction "2_2") (pintype "passive"))
      (node (ref "C3") (pin "1") (pinfunction "1_1") (pintype "passive"))
      (node (ref "C30") (pin "2") (pinfunction "2_2") (pintype "passive"))
      (node (ref "C31") (pin "2") (pinfunction "2_2") (pintype "passive"))
      (node (ref "C32") (pin "2") (pinfunction "2_2") (pintype "passive"))
      (node (ref "C33") (pin "2") (pinfunction "2_2") (pintype "passive"))
      (node (ref "C34") (pin "2") (pinfunction "2_2") (pintype "passive"))
      (node (ref "C35") (pin "1") (pinfunction "1_1") (pintype "passive"))
      (node (ref "C36") (pin "1") (pinfunction "1_1") (pintype "passive"))
      (node (ref "C37") (pin "1") (pinfunction "1_1") (pintype "passive"))
      (node (ref "C39") (pin "1") (pinfunction "1_1") (pintype "passive"))
      (node (ref "C4") (pin "1") (pinfunction "1_1") (pintype "passive"))
      (node (ref "C5") (pin "2") (pinfunction "2_2") (pintype "passive"))
      (node (ref "C6") (pin "2") (pinfunction "2_2") (pintype "passive"))
      (node (ref "C7") (pin "2") (pinfunction "2_2") (pintype "passive"))
      (node (ref "C8") (pin "2") (pinfunction "2_2") (pintype "passive"))
      (node (ref "C9") (pin "2") (pinfunction "2_2") (pintype "passive"))
      (node (ref "IC1") (pin "3") (pinfunction "A2_3") (pintype "input"))
      (node (ref "IC1") (pin "4") (pinfunction "GND_4") (pintype "power_in"))
      (node (ref "J1") (pin "1") (pinfunction "SHIELD_1") (pintype "bidirectional"))
      (node (ref "J1") (pin "2") (pinfunction "SHIELD_2") (pintype "bidirectional"))
      (node (ref "J1") (pin "3") (pinfunction "SHIELD_3") (pintype "bidirectional"))
      (node (ref "J1") (pin "4") (pinfunction "SHIELD_4") (pintype "bidirectional"))
      (node (ref "J1") (pin "5") (pinfunction "SHIELD_5") (pintype "bidirectional"))
      (node (ref "J1") (pin "6") (pinfunction "SHIELD_6") (pintype "bidirectional"))
      (node (ref "J2") (pin "401") (pinfunction "P$1_401") (pintype "bidirectional"))
      (node (ref "J2") (pin "402") (pinfunction "P$1_402") (pintype "bidirectional"))
      (node (ref "J2") (pin "A1") (pinfunction "A1_A1") (pintype "passive"))
      (node (ref "J2") (pin "A12") (pinfunction "A12_A12") (pintype "passive"))
      (node (ref "J2") (pin "A13") (pinfunction "A13_A13") (pintype "passive"))
      (node (ref "J2") (pin "A16") (pinfunction "A16_A16") (pintype "passive"))
      (node (ref "J2") (pin "A17") (pinfunction "A17_A17") (pintype "passive"))
      (node (ref "J2") (pin "A20") (pinfunction "A20_A20") (pintype "passive"))
      (node (ref "J2") (pin "A21") (pinfunction "A21_A21") (pintype "passive"))
      (node (ref "J2") (pin "A24") (pinfunction "A24_A24") (pintype "passive"))
      (node (ref "J2") (pin "A25") (pinfunction "A25_A25") (pintype "passive"))
      (node (ref "J2") (pin "A28") (pinfunction "A28_A28") (pintype "passive"))
      (node (ref "J2") (pin "A29") (pinfunction "A29_A29") (pintype "passive"))
      (node (ref "J2") (pin "A32") (pinfunction "A32_A32") (pintype "passive"))
      (node (ref "J2") (pin "A33") (pinfunction "A33_A33") (pintype "passive"))
      (node (ref "J2") (pin "A36") (pinfunction "A36_A36") (pintype "passive"))
      (node (ref "J2") (pin "A37") (pinfunction "A37_A37") (pintype "passive"))
      (node (ref "J2") (pin "A4") (pinfunction "A4_A4") (pintype "passive"))
      (node (ref "J2") (pin "A40") (pinfunction "A40_A40") (pintype "passive"))
      (node (ref "J2") (pin "A5") (pinfunction "A5_A5") (pintype "passive"))
      (node (ref "J2") (pin "A8") (pinfunction "A8_A8") (pintype "passive"))
      (node (ref "J2") (pin "A9") (pinfunction "A9_A9") (pintype "passive"))
      (node (ref "J2") (pin "B10") (pinfunction "B10_B10") (pintype "passive"))
      (node (ref "J2") (pin "B11") (pinfunction "B11_B11") (pintype "passive"))
      (node (ref "J2") (pin "B14") (pinfunction "B14_B14") (pintype "passive"))
      (node (ref "J2") (pin "B15") (pinfunction "B15_B15") (pintype "passive"))
      (node (ref "J2") (pin "B18") (pinfunction "B18_B18") (pintype "passive"))
      (node (ref "J2") (pin "B19") (pinfunction "B19_B19") (pintype "passive"))
      (node (ref "J2") (pin "B2") (pinfunction "B2_B2") (pintype "passive"))
      (node (ref "J2") (pin "B22") (pinfunction "B22_B22") (pintype "passive"))
      (node (ref "J2") (pin "B23") (pinfunction "B23_B23") (pintype "passive"))
      (node (ref "J2") (pin "B26") (pinfunction "B26_B26") (pintype "passive"))
      (node (ref "J2") (pin "B27") (pinfunction "B27_B27") (pintype "passive"))
      (node (ref "J2") (pin "B3") (pinfunction "B3_B3") (pintype "passive"))
      (node (ref "J2") (pin "B30") (pinfunction "B30_B30") (pintype "passive"))
      (node (ref "J2") (pin "B31") (pinfunction "B31_B31") (pintype "passive"))
      (node (ref "J2") (pin "B34") (pinfunction "B34_B34") (pintype "passive"))
      (node (ref "J2") (pin "B35") (pinfunction "B35_B35") (pintype "passive"))
      (node (ref "J2") (pin "B38") (pinfunction "B38_B38") (pintype "passive"))
      (node (ref "J2") (pin "B39") (pinfunction "B39_B39") (pintype "passive"))
      (node (ref "J2") (pin "B6") (pinfunction "B6_B6") (pintype "passive"))
      (node (ref "J2") (pin "B7") (pinfunction "B7_B7") (pintype "passive"))
      (node (ref "J2") (pin "C1") (pinfunction "C1_C1") (pintype "passive"))
      (node (ref "J2") (pin "C12") (pinfunction "C12_C12") (pintype "passive"))
      (node (ref "J2") (pin "C13") (pinfunction "C13_C13") (pintype "passive"))
      (node (ref "J2") (pin "C16") (pinfunction "C16_C16") (pintype "passive"))
      (node (ref "J2") (pin "C17") (pinfunction "C17_C17") (pintype "passive"))
      (node (ref "J2") (pin "C20") (pinfunction "C20_C20") (pintype "passive"))
      (node (ref "J2") (pin "C21") (pinfunction "C21_C21") (pintype "passive"))
      (node (ref "J2") (pin "C24") (pinfunction "C24_C24") (pintype "passive"))
      (node (ref "J2") (pin "C25") (pinfunction "C25_C25") (pintype "passive"))
      (node (ref "J2") (pin "C28") (pinfunction "C28_C28") (pintype "passive"))
      (node (ref "J2") (pin "C29") (pinfunction "C29_C29") (pintype "passive"))
      (node (ref "J2") (pin "C32") (pinfunction "C32_C32") (pintype "passive"))
      (node (ref "J2") (pin "C33") (pinfunction "C33_C33") (pintype "passive"))
      (node (ref "J2") (pin "C36") (pinfunction "C36_C36") (pintype "passive"))
      (node (ref "J2") (pin "C38") (pinfunction "C38_C38") (pintype "passive"))
      (node (ref "J2") (pin "C4") (pinfunction "C4_C4") (pintype "passive"))
      (node (ref "J2") (pin "C40") (pinfunction "C40_C40") (pintype "passive"))
      (node (ref "J2") (pin "C5") (pinfunction "C5_C5") (pintype "passive"))
      (node (ref "J2") (pin "C8") (pinfunction "C8_C8") (pintype "passive"))
      (node (ref "J2") (pin "C9") (pinfunction "C9_C9") (pintype "passive"))
      (node (ref "J2") (pin "D10") (pinfunction "D10_D10") (pintype "passive"))
      (node (ref "J2") (pin "D13") (pinfunction "D13_D13") (pintype "passive"))
      (node (ref "J2") (pin "D16") (pinfunction "D16_D16") (pintype "passive"))
      (node (ref "J2") (pin "D19") (pinfunction "D19_D19") (pintype "passive"))
      (node (ref "J2") (pin "D2") (pinfunction "D2_D2") (pintype "passive"))
      (node (ref "J2") (pin "D22") (pinfunction "D22_D22") (pintype "passive"))
      (node (ref "J2") (pin "D25") (pinfunction "D25_D25") (pintype "passive"))
      (node (ref "J2") (pin "D28") (pinfunction "D28_D28") (pintype "passive"))
      (node (ref "J2") (pin "D3") (pinfunction "D3_D3") (pintype "passive"))
      (node (ref "J2") (pin "D37") (pinfunction "D37_D37") (pintype "passive"))
      (node (ref "J2") (pin "D39") (pinfunction "D39_D39") (pintype "passive"))
      (node (ref "J2") (pin "D6") (pinfunction "D6_D6") (pintype "passive"))
      (node (ref "J2") (pin "D7") (pinfunction "D7_D7") (pintype "passive"))
      (node (ref "J2") (pin "E1") (pinfunction "E1_E1") (pintype "passive"))
      (node (ref "J2") (pin "E11") (pinfunction "E11_E11") (pintype "passive"))
      (node (ref "J2") (pin "E14") (pinfunction "E14_E14") (pintype "passive"))
      (node (ref "J2") (pin "E17") (pinfunction "E17_E17") (pintype "passive"))
      (node (ref "J2") (pin "E20") (pinfunction "E20_E20") (pintype "passive"))
      (node (ref "J2") (pin "E23") (pinfunction "E23_E23") (pintype "passive"))
      (node (ref "J2") (pin "E26") (pinfunction "E26_E26") (pintype "passive"))
      (node (ref "J2") (pin "E29") (pinfunction "E29_E29") (pintype "passive"))
      (node (ref "J2") (pin "E32") (pinfunction "E32_E32") (pintype "passive"))
      (node (ref "J2") (pin "E35") (pinfunction "E35_E35") (pintype "passive"))
      (node (ref "J2") (pin "E38") (pinfunction "E38_E38") (pintype "passive"))
      (node (ref "J2") (pin "E4") (pinfunction "E4_E4") (pintype "passive"))
      (node (ref "J2") (pin "E40") (pinfunction "E40_E40") (pintype "passive"))
      (node (ref "J2") (pin "E5") (pinfunction "E5_E5") (pintype "passive"))
      (node (ref "J2") (pin "E8") (pinfunction "E8_E8") (pintype "passive"))
      (node (ref "J2") (pin "F12") (pinfunction "F12_F12") (pintype "passive"))
      (node (ref "J2") (pin "F15") (pinfunction "F15_F15") (pintype "passive"))
      (node (ref "J2") (pin "F18") (pinfunction "F18_F18") (pintype "passive"))
      (node (ref "J2") (pin "F2") (pinfunction "F2_F2") (pintype "passive"))
      (node (ref "J2") (pin "F21") (pinfunction "F21_F21") (pintype "passive"))
      (node (ref "J2") (pin "F24") (pinfunction "F24_F24") (pintype "passive"))
      (node (ref "J2") (pin "F27") (pinfunction "F27_F27") (pintype "passive"))
      (node (ref "J2") (pin "F3") (pinfunction "F3_F3") (pintype "passive"))
      (node (ref "J2") (pin "F30") (pinfunction "F30_F30") (pintype "passive"))
      (node (ref "J2") (pin "F33") (pinfunction "F33_F33") (pintype "passive"))
      (node (ref "J2") (pin "F36") (pinfunction "F36_F36") (pintype "passive"))
      (node (ref "J2") (pin "F39") (pinfunction "F39_F39") (pintype "passive"))
      (node (ref "J2") (pin "F6") (pinfunction "F6_F6") (pintype "passive"))
      (node (ref "J2") (pin "F9") (pinfunction "F9_F9") (pintype "passive"))
      (node (ref "J2") (pin "G1") (pinfunction "G1_G1") (pintype "passive"))
      (node (ref "J2") (pin "G11") (pinfunction "G11_G11") (pintype "passive"))
      (node (ref "J2") (pin "G14") (pinfunction "G14_G14") (pintype "passive"))
      (node (ref "J2") (pin "G17") (pinfunction "G17_G17") (pintype "passive"))
      (node (ref "J2") (pin "G20") (pinfunction "G20_G20") (pintype "passive"))
      (node (ref "J2") (pin "G23") (pinfunction "G23_G23") (pintype "passive"))
      (node (ref "J2") (pin "G26") (pinfunction "G26_G26") (pintype "passive"))
      (node (ref "J2") (pin "G29") (pinfunction "G29_G29") (pintype "passive"))
      (node (ref "J2") (pin "G32") (pinfunction "G32_G32") (pintype "passive"))
      (node (ref "J2") (pin "G35") (pinfunction "G35_G35") (pintype "passive"))
      (node (ref "J2") (pin "G38") (pinfunction "G38_G38") (pintype "passive"))
      (node (ref "J2") (pin "G4") (pinfunction "G4_G4") (pintype "passive"))
      (node (ref "J2") (pin "G40") (pinfunction "G40_G40") (pintype "passive"))
      (node (ref "J2") (pin "G5") (pinfunction "G5_G5") (pintype "passive"))
      (node (ref "J2") (pin "G8") (pinfunction "G8_G8") (pintype "passive"))
      (node (ref "J2") (pin "H12") (pinfunction "H12_H12") (pintype "passive"))
      (node (ref "J2") (pin "H15") (pinfunction "H15_H15") (pintype "passive"))
      (node (ref "J2") (pin "H18") (pinfunction "H18_H18") (pintype "passive"))
      (node (ref "J2") (pin "H2") (pinfunction "H2_H2") (pintype "passive"))
      (node (ref "J2") (pin "H21") (pinfunction "H21_H21") (pintype "passive"))
      (node (ref "J2") (pin "H24") (pinfunction "H24_H24") (pintype "passive"))
      (node (ref "J2") (pin "H27") (pinfunction "H27_H27") (pintype "passive"))
      (node (ref "J2") (pin "H3") (pinfunction "H3_H3") (pintype "passive"))
      (node (ref "J2") (pin "H30") (pinfunction "H30_H30") (pintype "passive"))
      (node (ref "J2") (pin "H33") (pinfunction "H33_H33") (pintype "passive"))
      (node (ref "J2") (pin "H36") (pinfunction "H36_H36") (pintype "passive"))
      (node (ref "J2") (pin "H39") (pinfunction "H39_H39") (pintype "passive"))
      (node (ref "J2") (pin "H6") (pinfunction "H6_H6") (pintype "passive"))
      (node (ref "J2") (pin "H9") (pinfunction "H9_H9") (pintype "passive"))
      (node (ref "J2") (pin "J1") (pinfunction "J1_J1") (pintype "passive"))
      (node (ref "J2") (pin "J11") (pinfunction "J11_J11") (pintype "passive"))
      (node (ref "J2") (pin "J14") (pinfunction "J14_J14") (pintype "passive"))
      (node (ref "J2") (pin "J17") (pinfunction "J17_J17") (pintype "passive"))
      (node (ref "J2") (pin "J20") (pinfunction "J20_J20") (pintype "passive"))
      (node (ref "J2") (pin "J23") (pinfunction "J23_J23") (pintype "passive"))
      (node (ref "J2") (pin "J26") (pinfunction "J26_J26") (pintype "passive"))
      (node (ref "J2") (pin "J29") (pinfunction "J29_J29") (pintype "passive"))
      (node (ref "J2") (pin "J32") (pinfunction "J32_J32") (pintype "passive"))
      (node (ref "J2") (pin "J35") (pinfunction "J35_J35") (pintype "passive"))
      (node (ref "J2") (pin "J38") (pinfunction "J38_J38") (pintype "passive"))
      (node (ref "J2") (pin "J4") (pinfunction "J4_J4") (pintype "passive"))
      (node (ref "J2") (pin "J40") (pinfunction "J40_J40") (pintype "passive"))
      (node (ref "J2") (pin "J5") (pinfunction "J5_J5") (pintype "passive"))
      (node (ref "J2") (pin "J8") (pinfunction "J8_J8") (pintype "passive"))
      (node (ref "J2") (pin "K12") (pinfunction "K12_K12") (pintype "passive"))
      (node (ref "J2") (pin "K15") (pinfunction "K15_K15") (pintype "passive"))
      (node (ref "J2") (pin "K18") (pinfunction "K18_K18") (pintype "passive"))
      (node (ref "J2") (pin "K2") (pinfunction "K2_K2") (pintype "passive"))
      (node (ref "J2") (pin "K21") (pinfunction "K21_K21") (pintype "passive"))
      (node (ref "J2") (pin "K24") (pinfunction "K24_K24") (pintype "passive"))
      (node (ref "J2") (pin "K27") (pinfunction "K27_K27") (pintype "passive"))
      (node (ref "J2") (pin "K3") (pinfunction "K3_K3") (pintype "passive"))
      (node (ref "J2") (pin "K30") (pinfunction "K30_K30") (pintype "passive"))
      (node (ref "J2") (pin "K33") (pinfunction "K33_K33") (pintype "passive"))
      (node (ref "J2") (pin "K36") (pinfunction "K36_K36") (pintype "passive"))
      (node (ref "J2") (pin "K39") (pinfunction "K39_K39") (pintype "passive"))
      (node (ref "J2") (pin "K6") (pinfunction "K6_K6") (pintype "passive"))
      (node (ref "J2") (pin "K9") (pinfunction "K9_K9") (pintype "passive"))
      (node (ref "JP1") (pin "7") (pinfunction "7_7") (pintype "passive"))
      (node (ref "JP1") (pin "8") (pinfunction "8_8") (pintype "passive"))
      (node (ref "R53") (pin "1") (pinfunction "1_1") (pintype "passive"))
      (node (ref "R54") (pin "1") (pinfunction "1_1") (pintype "passive"))
      (node (ref "R55") (pin "1") (pinfunction "1_1") (pintype "passive"))
      (node (ref "R56") (pin "1") (pinfunction "1_1") (pintype "passive"))
      (node (ref "R59") (pin "2") (pinfunction "2_2") (pintype "passive"))
      (node (ref "R61") (pin "2") (pinfunction "2_2") (pintype "passive"))
      (node (ref "U1") (pin "P5") (pinfunction "GND_P5") (pintype "bidirectional"))
      (node (ref "U10") (pin "P5") (pinfunction "GND_P5") (pintype "bidirectional"))
      (node (ref "U11") (pin "P5") (pinfunction "GND_P5") (pintype "bidirectional"))
      (node (ref "U12") (pin "P5") (pinfunction "GND_P5") (pintype "bidirectional"))
      (node (ref "U13") (pin "P5") (pinfunction "GND_P5") (pintype "bidirectional"))
      (node (ref "U14") (pin "P5") (pinfunction "GND_P5") (pintype "bidirectional"))
      (node (ref "U15") (pin "P5") (pinfunction "GND_P5") (pintype "bidirectional"))
      (node (ref "U16") (pin "P5") (pinfunction "GND_P5") (pintype "bidirectional"))
      (node (ref "U17") (pin "P0") (pinfunction "A0_P0") (pintype "bidirectional"))
      (node (ref "U17") (pin "P1") (pinfunction "A1_P1") (pintype "bidirectional"))
      (node (ref "U17") (pin "P11") (pinfunction "GND_P11") (pintype "bidirectional"))
      (node (ref "U17") (pin "P20") (pinfunction "A2_P20") (pintype "bidirectional"))
      (node (ref "U18") (pin "2") (pinfunction "GND_2") (pintype "bidirectional"))
      (node (ref "U19") (pin "2") (pinfunction "GND_2") (pintype "bidirectional"))
      (node (ref "U2") (pin "P5") (pinfunction "GND_P5") (pintype "bidirectional"))
      (node (ref "U20") (pin "2") (pinfunction "GND_2") (pintype "bidirectional"))
      (node (ref "U21") (pin "2") (pinfunction "GND_2") (pintype "bidirectional"))
      (node (ref "U3") (pin "P5") (pinfunction "GND_P5") (pintype "bidirectional"))
      (node (ref "U4") (pin "P5") (pinfunction "GND_P5") (pintype "bidirectional"))
      (node (ref "U40") (pin "P2") (pinfunction "S_P2") (pintype "passive"))
      (node (ref "U5") (pin "P5") (pinfunction "GND_P5") (pintype "bidirectional"))
      (node (ref "U6") (pin "P5") (pinfunction "GND_P5") (pintype "bidirectional"))
      (node (ref "U7") (pin "P5") (pinfunction "GND_P5") (pintype "bidirectional"))
      (node (ref "U8") (pin "P5") (pinfunction "GND_P5") (pintype "bidirectional"))
      (node (ref "U9") (pin "P5") (pinfunction "GND_P5") (pintype "bidirectional"))
      (node (ref "X1") (pin "1") (pinfunction "KL_1") (pintype "passive"))
    )
    (net (code "4") (name "1V8") (class "Default")
      (node (ref "C1") (pin "1") (pinfunction "1_1") (pintype "passive"))
      (node (ref "C11") (pin "1") (pinfunction "1_1") (pintype "passive"))
      (node (ref "C13") (pin "1") (pinfunction "1_1") (pintype "passive"))
      (node (ref "C15") (pin "1") (pinfunction "1_1") (pintype "passive"))
      (node (ref "C17") (pin "1") (pinfunction "1_1") (pintype "passive"))
      (node (ref "C19") (pin "1") (pinfunction "1_1") (pintype "passive"))
      (node (ref "C21") (pin "1") (pinfunction "1_1") (pintype "passive"))
      (node (ref "C23") (pin "1") (pinfunction "1_1") (pintype "passive"))
      (node (ref "C25") (pin "1") (pinfunction "1_1") (pintype "passive"))
      (node (ref "C27") (pin "1") (pinfunction "1_1") (pintype "passive"))
      (node (ref "C29") (pin "1") (pinfunction "1_1") (pintype "passive"))
      (node (ref "C3") (pin "2") (pinfunction "2_2") (pintype "passive"))
      (node (ref "C31") (pin "1") (pinfunction "1_1") (pintype "passive"))
      (node (ref "C33") (pin "1") (pinfunction "1_1") (pintype "passive"))
      (node (ref "C4") (pin "2") (pinfunction "2_2") (pintype "passive"))
      (node (ref "C5") (pin "1") (pinfunction "1_1") (pintype "passive"))
      (node (ref "C7") (pin "1") (pinfunction "1_1") (pintype "passive"))
      (node (ref "C9") (pin "1") (pinfunction "1_1") (pintype "passive"))
      (node (ref "JP1") (pin "1") (pinfunction "1_1") (pintype "passive"))
      (node (ref "R5") (pin "2") (pinfunction "2_2") (pintype "passive"))
      (node (ref "R6") (pin "2") (pinfunction "2_2") (pintype "passive"))
      (node (ref "R60") (pin "2") (pinfunction "2_2") (pintype "passive"))
      (node (ref "R7") (pin "2") (pinfunction "2_2") (pintype "passive"))
      (node (ref "U1") (pin "P0") (pinfunction "VIO_P0") (pintype "bidirectional"))
      (node (ref "U10") (pin "P0") (pinfunction "VIO_P0") (pintype "bidirectional"))
      (node (ref "U11") (pin "P0") (pinfunction "VIO_P0") (pintype "bidirectional"))
      (node (ref "U12") (pin "P0") (pinfunction "VIO_P0") (pintype "bidirectional"))
      (node (ref "U13") (pin "P0") (pinfunction "VIO_P0") (pintype "bidirectional"))
      (node (ref "U14") (pin "P0") (pinfunction "VIO_P0") (pintype "bidirectional"))
      (node (ref "U15") (pin "P0") (pinfunction "VIO_P0") (pintype "bidirectional"))
      (node (ref "U16") (pin "P0") (pinfunction "VIO_P0") (pintype "bidirectional"))
      (node (ref "U17") (pin "P23") (pinfunction "VCC_P23") (pintype "bidirectional"))
      (node (ref "U18") (pin "3") (pinfunction "VCCA_3") (pintype "bidirectional"))
      (node (ref "U19") (pin "3") (pinfunction "VCCA_3") (pintype "bidirectional"))
      (node (ref "U2") (pin "P0") (pinfunction "VIO_P0") (pintype "bidirectional"))
      (node (ref "U20") (pin "3") (pinfunction "VCCA_3") (pintype "bidirectional"))
      (node (ref "U21") (pin "3") (pinfunction "VCCA_3") (pintype "bidirectional"))
      (node (ref "U3") (pin "P0") (pinfunction "VIO_P0") (pintype "bidirectional"))
      (node (ref "U4") (pin "P0") (pinfunction "VIO_P0") (pintype "bidirectional"))
      (node (ref "U5") (pin "P0") (pinfunction "VIO_P0") (pintype "bidirectional"))
      (node (ref "U6") (pin "P0") (pinfunction "VIO_P0") (pintype "bidirectional"))
      (node (ref "U7") (pin "P0") (pinfunction "VIO_P0") (pintype "bidirectional"))
      (node (ref "U8") (pin "P0") (pinfunction "VIO_P0") (pintype "bidirectional"))
      (node (ref "U9") (pin "P0") (pinfunction "VIO_P0") (pintype "bidirectional"))
    )
    (net (code "5") (name "1V8_POWER_GOOD") (class "Default")
      (node (ref "J2") (pin "D1") (pinfunction "D1_D1") (pintype "passive"))
      (node (ref "R58") (pin "1") (pinfunction "1_1") (pintype "passive"))
    )
    (net (code "6") (name "3P3VAUX") (class "Default")
      (node (ref "C39") (pin "2") (pinfunction "2_2") (pintype "passive"))
      (node (ref "IC1") (pin "8") (pinfunction "VCC_8") (pintype "power_in"))
      (node (ref "J2") (pin "D32") (pinfunction "D32_D32") (pintype "passive"))
      (node (ref "R52") (pin "2") (pinfunction "2_2") (pintype "passive"))
    )
    (net (code "7") (name "5V") (class "Default")
      (node (ref "5V_GOOD") (pin "A") (pinfunction "A_A") (pintype "passive"))
      (node (ref "C10") (pin "1") (pinfunction "1_1") (pintype "passive"))
      (node (ref "C12") (pin "1") (pinfunction "1_1") (pintype "passive"))
      (node (ref "C14") (pin "1") (pinfunction "1_1") (pintype "passive"))
      (node (ref "C16") (pin "1") (pinfunction "1_1") (pintype "passive"))
      (node (ref "C18") (pin "1") (pinfunction "1_1") (pintype "passive"))
      (node (ref "C2") (pin "1") (pinfunction "1_1") (pintype "passive"))
      (node (ref "C20") (pin "1") (pinfunction "1_1") (pintype "passive"))
      (node (ref "C22") (pin "1") (pinfunction "1_1") (pintype "passive"))
      (node (ref "C24") (pin "1") (pinfunction "1_1") (pintype "passive"))
      (node (ref "C26") (pin "1") (pinfunction "1_1") (pintype "passive"))
      (node (ref "C28") (pin "1") (pinfunction "1_1") (pintype "passive"))
      (node (ref "C30") (pin "1") (pinfunction "1_1") (pintype "passive"))
      (node (ref "C32") (pin "1") (pinfunction "1_1") (pintype "passive"))
      (node (ref "C34") (pin "1") (pinfunction "1_1") (pintype "passive"))
      (node (ref "C6") (pin "1") (pinfunction "1_1") (pintype "passive"))
      (node (ref "C8") (pin "1") (pinfunction "1_1") (pintype "passive"))
      (node (ref "J1") (pin "1.4") (pinfunction "1.4_1.4") (pintype "passive"))
      (node (ref "J1") (pin "2.4") (pinfunction "2.4_2.4") (pintype "passive"))
      (node (ref "J1") (pin "3.4") (pinfunction "3.4_3.4") (pintype "passive"))
      (node (ref "J1") (pin "4.4") (pinfunction "4.4_4.4") (pintype "passive"))
      (node (ref "J1") (pin "5.5") (pinfunction "5.4_5.5") (pintype "passive"))
      (node (ref "J1") (pin "6.5") (pinfunction "6.4_6.5") (pintype "passive"))
      (node (ref "J1") (pin "7.5") (pinfunction "7.4_7.5") (pintype "passive"))
      (node (ref "J1") (pin "8.5") (pinfunction "8.4_8.5") (pintype "passive"))
      (node (ref "JP1") (pin "5") (pinfunction "5_5") (pintype "passive"))
      (node (ref "JP1") (pin "6") (pinfunction "6_6") (pintype "passive"))
      (node (ref "R10") (pin "2") (pinfunction "2_2") (pintype "passive"))
      (node (ref "R11") (pin "2") (pinfunction "2_2") (pintype "passive"))
      (node (ref "R12") (pin "2") (pinfunction "2_2") (pintype "passive"))
      (node (ref "R13") (pin "2") (pinfunction "2_2") (pintype "passive"))
      (node (ref "R14") (pin "2") (pinfunction "2_2") (pintype "passive"))
      (node (ref "R15") (pin "2") (pinfunction "2_2") (pintype "passive"))
      (node (ref "R16") (pin "2") (pinfunction "2_2") (pintype "passive"))
      (node (ref "R17") (pin "2") (pinfunction "2_2") (pintype "passive"))
      (node (ref "R18") (pin "2") (pinfunction "2_2") (pintype "passive"))
      (node (ref "R19") (pin "2") (pinfunction "2_2") (pintype "passive"))
      (node (ref "R20") (pin "2") (pinfunction "2_2") (pintype "passive"))
      (node (ref "R21") (pin "2") (pinfunction "2_2") (pintype "passive"))
      (node (ref "R3") (pin "2") (pinfunction "2_2") (pintype "passive"))
      (node (ref "R4") (pin "2") (pinfunction "2_2") (pintype "passive"))
      (node (ref "R8") (pin "2") (pinfunction "2_2") (pintype "passive"))
      (node (ref "R9") (pin "2") (pinfunction "2_2") (pintype "passive"))
      (node (ref "U1") (pin "P9") (pinfunction "VCC_P9") (pintype "bidirectional"))
      (node (ref "U10") (pin "P9") (pinfunction "VCC_P9") (pintype "bidirectional"))
      (node (ref "U11") (pin "P9") (pinfunction "VCC_P9") (pintype "bidirectional"))
      (node (ref "U12") (pin "P9") (pinfunction "VCC_P9") (pintype "bidirectional"))
      (node (ref "U13") (pin "P9") (pinfunction "VCC_P9") (pintype "bidirectional"))
      (node (ref "U14") (pin "P9") (pinfunction "VCC_P9") (pintype "bidirectional"))
      (node (ref "U15") (pin "P9") (pinfunction "VCC_P9") (pintype "bidirectional"))
      (node (ref "U16") (pin "P9") (pinfunction "VCC_P9") (pintype "bidirectional"))
      (node (ref "U18") (pin "7") (pinfunction "VCCB_7") (pintype "bidirectional"))
      (node (ref "U19") (pin "7") (pinfunction "VCCB_7") (pintype "bidirectional"))
      (node (ref "U2") (pin "P9") (pinfunction "VCC_P9") (pintype "bidirectional"))
      (node (ref "U20") (pin "7") (pinfunction "VCCB_7") (pintype "bidirectional"))
      (node (ref "U21") (pin "7") (pinfunction "VCCB_7") (pintype "bidirectional"))
      (node (ref "U3") (pin "P9") (pinfunction "VCC_P9") (pintype "bidirectional"))
      (node (ref "U4") (pin "P9") (pinfunction "VCC_P9") (pintype "bidirectional"))
      (node (ref "U5") (pin "P9") (pinfunction "VCC_P9") (pintype "bidirectional"))
      (node (ref "U6") (pin "P9") (pinfunction "VCC_P9") (pintype "bidirectional"))
      (node (ref "U7") (pin "P9") (pinfunction "VCC_P9") (pintype "bidirectional"))
      (node (ref "U8") (pin "P9") (pinfunction "VCC_P9") (pintype "bidirectional"))
      (node (ref "U9") (pin "P9") (pinfunction "VCC_P9") (pintype "bidirectional"))
      (node (ref "X1") (pin "2") (pinfunction "KL_2") (pintype "passive"))
    )
    (net (code "8") (name "CONV_OE") (class "Default")
      (node (ref "R55") (pin "2") (pinfunction "2_2") (pintype "passive"))
      (node (ref "R57") (pin "1") (pinfunction "1_1") (pintype "passive"))
      (node (ref "R58") (pin "2") (pinfunction "2_2") (pintype "passive"))
      (node (ref "U18") (pin "6") (pinfunction "OE_6") (pintype "bidirectional"))
      (node (ref "U19") (pin "6") (pinfunction "OE_6") (pintype "bidirectional"))
      (node (ref "U20") (pin "6") (pinfunction "OE_6") (pintype "bidirectional"))
      (node (ref "U21") (pin "6") (pinfunction "OE_6") (pintype "bidirectional"))
    )
    (net (code "9") (name "FLOATING1") (class "Default")
      (node (ref "J2") (pin "B1") (pinfunction "B1_B1") (pintype "passive"))
    )
    (net (code "10") (name "FLOATING2") (class "Default")
      (node (ref "J2") (pin "B40") (pinfunction "B40_B40") (pintype "passive"))
    )
    (net (code "11") (name "FMC_CLK0_M2C_N") (class "Default")
      (node (ref "J2") (pin "H5") (pinfunction "H5_H5") (pintype "passive"))
    )
    (net (code "12") (name "FMC_CLK0_M2C_P") (class "Default")
      (node (ref "J2") (pin "H4") (pinfunction "H4_H4") (pintype "passive"))
    )
    (net (code "13") (name "FMC_CLK1_M2C_N") (class "Default")
      (node (ref "J2") (pin "G3") (pinfunction "G3_G3") (pintype "passive"))
    )
    (net (code "14") (name "FMC_CLK1_M2C_P") (class "Default")
      (node (ref "J2") (pin "G2") (pinfunction "G2_G2") (pintype "passive"))
    )
    (net (code "15") (name "FMC_DP0_C2M_N") (class "Default")
      (node (ref "J2") (pin "C3") (pinfunction "C3_C3") (pintype "passive"))
    )
    (net (code "16") (name "FMC_DP0_C2M_P") (class "Default")
      (node (ref "J2") (pin "C2") (pinfunction "C2_C2") (pintype "passive"))
    )
    (net (code "17") (name "FMC_DP0_M2C_N") (class "Default")
      (node (ref "J2") (pin "C7") (pinfunction "C7_C7") (pintype "passive"))
      (node (ref "JP1") (pin "19") (pinfunction "19_19") (pintype "passive"))
    )
    (net (code "18") (name "FMC_DP0_M2C_P") (class "Default")
      (node (ref "J2") (pin "C6") (pinfunction "C6_C6") (pintype "passive"))
      (node (ref "JP1") (pin "20") (pinfunction "20_20") (pintype "passive"))
    )
    (net (code "19") (name "FMC_GBTCLK0_M2C_N") (class "Default")
      (node (ref "J2") (pin "D5") (pinfunction "D5_D5") (pintype "passive"))
    )
    (net (code "20") (name "FMC_GBTCLK0_M2C_P") (class "Default")
      (node (ref "J2") (pin "D4") (pinfunction "D4_D4") (pintype "passive"))
    )
    (net (code "21") (name "FMC_IIC_SCL") (class "Default")
      (node (ref "EESCL") (pin "TP") (pinfunction "TP_TP") (pintype "input"))
      (node (ref "IC1") (pin "6") (pinfunction "SCL_6") (pintype "input"))
      (node (ref "J2") (pin "C30") (pinfunction "C30_C30") (pintype "passive"))
      (node (ref "JP1") (pin "10") (pinfunction "10_10") (pintype "passive"))
      (node (ref "R64") (pin "1") (pinfunction "1_1") (pintype "passive"))
    )
    (net (code "22") (name "FMC_IIC_SDA") (class "Default")
      (node (ref "EESDA") (pin "TP") (pinfunction "TP_TP") (pintype "input"))
      (node (ref "IC1") (pin "5") (pinfunction "SDA_5") (pintype "bidirectional"))
      (node (ref "J2") (pin "C31") (pinfunction "C31_C31") (pintype "passive"))
      (node (ref "JP1") (pin "9") (pinfunction "9_9") (pintype "passive"))
      (node (ref "R63") (pin "1") (pinfunction "1_1") (pintype "passive"))
    )
    (net (code "23") (name "FMC_LA00_CC_N") (class "Default")
      (node (ref "J2") (pin "G7") (pinfunction "G7_G7") (pintype "passive"))
      (node (ref "RJ1_FCD") (pin "TP") (pinfunction "TP_TP") (pintype "input"))
      (node (ref "U13") (pin "P2") (pinfunction "DE_P2") (pintype "bidirectional"))
      (node (ref "U13") (pin "P3") (pinfunction "RE_P3") (pintype "bidirectional"))
    )
    (net (code "24") (name "FMC_LA00_CC_P") (class "Default")
      (node (ref "J2") (pin "G6") (pinfunction "G6_G6") (pintype "passive"))
      (node (ref "R45") (pin "2") (pinfunction "2_2") (pintype "passive"))
      (node (ref "RJ1_FCL") (pin "TP") (pinfunction "TP_TP") (pintype "input"))
    )
    (net (code "25") (name "FMC_LA01_CC_N") (class "Default")
      (node (ref "J2") (pin "D9") (pinfunction "D9_D9") (pintype "passive"))
      (node (ref "R51") (pin "2") (pinfunction "2_2") (pintype "passive"))
    )
    (net (code "26") (name "FMC_LA01_CC_P") (class "Default")
      (node (ref "J2") (pin "D8") (pinfunction "D8_D8") (pintype "passive"))
      (node (ref "U16") (pin "P2") (pinfunction "DE_P2") (pintype "bidirectional"))
      (node (ref "U16") (pin "P3") (pinfunction "RE_P3") (pintype "bidirectional"))
    )
    (net (code "27") (name "FMC_LA02_N") (class "Default")
      (node (ref "J2") (pin "H8") (pinfunction "H8_H8") (pintype "passive"))
      (node (ref "U21") (pin "4") (pinfunction "A2_4") (pintype "bidirectional"))
    )
    (net (code "28") (name "FMC_LA02_P") (class "Default")
      (node (ref "J2") (pin "H7") (pinfunction "H7_H7") (pintype "passive"))
      (node (ref "RJ1_FC") (pin "TP") (pinfunction "TP_TP") (pintype "input"))
      (node (ref "U21") (pin "5") (pinfunction "A1_5") (pintype "bidirectional"))
    )
    (net (code "29") (name "FMC_LA03_N") (class "Default")
      (node (ref "J2") (pin "G10") (pinfunction "G10_G10") (pintype "passive"))
      (node (ref "U12") (pin "P2") (pinfunction "DE_P2") (pintype "bidirectional"))
      (node (ref "U12") (pin "P3") (pinfunction "RE_P3") (pintype "bidirectional"))
    )
    (net (code "30") (name "FMC_LA03_P") (class "Default")
      (node (ref "J2") (pin "G9") (pinfunction "G9_G9") (pintype "passive"))
      (node (ref "R43") (pin "2") (pinfunction "2_2") (pintype "passive"))
    )
    (net (code "31") (name "FMC_LA04_N") (class "Default")
      (node (ref "J2") (pin "H11") (pinfunction "H11_H11") (pintype "passive"))
      (node (ref "U11") (pin "P2") (pinfunction "DE_P2") (pintype "bidirectional"))
      (node (ref "U11") (pin "P3") (pinfunction "RE_P3") (pintype "bidirectional"))
    )
    (net (code "32") (name "FMC_LA04_P") (class "Default")
      (node (ref "J2") (pin "H10") (pinfunction "H10_H10") (pintype "passive"))
      (node (ref "R41") (pin "2") (pinfunction "2_2") (pintype "passive"))
    )
    (net (code "33") (name "FMC_LA05_N") (class "Default")
      (node (ref "J2") (pin "D12") (pinfunction "D12_D12") (pintype "passive"))
      (node (ref "RJ1_FDD") (pin "TP") (pinfunction "TP_TP") (pintype "input"))
      (node (ref "U14") (pin "P2") (pinfunction "DE_P2") (pintype "bidirectional"))
      (node (ref "U14") (pin "P3") (pinfunction "RE_P3") (pintype "bidirectional"))
    )
    (net (code "34") (name "FMC_LA05_P") (class "Default")
      (node (ref "J2") (pin "D11") (pinfunction "D11_D11") (pintype "passive"))
      (node (ref "R47") (pin "2") (pinfunction "2_2") (pintype "passive"))
      (node (ref "RJ1_FDA") (pin "TP") (pinfunction "TP_TP") (pintype "input"))
    )
    (net (code "35") (name "FMC_LA06_N") (class "Default")
      (node (ref "J2") (pin "C11") (pinfunction "C11_C11") (pintype "passive"))
      (node (ref "U15") (pin "P2") (pinfunction "DE_P2") (pintype "bidirectional"))
      (node (ref "U15") (pin "P3") (pinfunction "RE_P3") (pintype "bidirectional"))
    )
    (net (code "36") (name "FMC_LA06_P") (class "Default")
      (node (ref "J2") (pin "C10") (pinfunction "C10_C10") (pintype "passive"))
      (node (ref "R49") (pin "2") (pinfunction "2_2") (pintype "passive"))
    )
    (net (code "37") (name "FMC_LA07_N") (class "Default")
      (node (ref "J2") (pin "H14") (pinfunction "H14_H14") (pintype "passive"))
      (node (ref "RJ2_FDD") (pin "TP") (pinfunction "TP_TP") (pintype "input"))
      (node (ref "U10") (pin "P2") (pinfunction "DE_P2") (pintype "bidirectional"))
      (node (ref "U10") (pin "P3") (pinfunction "RE_P3") (pintype "bidirectional"))
    )
    (net (code "38") (name "FMC_LA07_P") (class "Default")
      (node (ref "J2") (pin "H13") (pinfunction "H13_H13") (pintype "passive"))
      (node (ref "R39") (pin "2") (pinfunction "2_2") (pintype "passive"))
      (node (ref "RJ2_FDA") (pin "TP") (pinfunction "TP_TP") (pintype "input"))
    )
    (net (code "39") (name "FMC_LA08_N") (class "Default")
      (node (ref "J2") (pin "G13") (pinfunction "G13_G13") (pintype "passive"))
    )
    (net (code "40") (name "FMC_LA08_P") (class "Default")
      (node (ref "J2") (pin "G12") (pinfunction "G12_G12") (pintype "passive"))
    )
    (net (code "41") (name "FMC_LA09_N") (class "Default")
      (node (ref "J2") (pin "D15") (pinfunction "D15_D15") (pintype "passive"))
      (node (ref "JP1") (pin "15") (pinfunction "15_15") (pintype "passive"))
    )
    (net (code "42") (name "FMC_LA09_P") (class "Default")
      (node (ref "J2") (pin "D14") (pinfunction "D14_D14") (pintype "passive"))
      (node (ref "JP1") (pin "16") (pinfunction "16_16") (pintype "passive"))
    )
    (net (code "43") (name "FMC_LA10_N") (class "Default")
      (node (ref "J2") (pin "C15") (pinfunction "C15_C15") (pintype "passive"))
      (node (ref "JP1") (pin "17") (pinfunction "17_17") (pintype "passive"))
    )
    (net (code "44") (name "FMC_LA10_P") (class "Default")
      (node (ref "J2") (pin "C14") (pinfunction "C14_C14") (pintype "passive"))
      (node (ref "JP1") (pin "18") (pinfunction "18_18") (pintype "passive"))
    )
    (net (code "45") (name "FMC_LA11_N") (class "Default")
      (node (ref "J2") (pin "H17") (pinfunction "H17_H17") (pintype "passive"))
      (node (ref "RJ2_FCD") (pin "TP") (pinfunction "TP_TP") (pintype "input"))
      (node (ref "U9") (pin "P2") (pinfunction "DE_P2") (pintype "bidirectional"))
      (node (ref "U9") (pin "P3") (pinfunction "RE_P3") (pintype "bidirectional"))
    )
    (net (code "46") (name "FMC_LA11_P") (class "Default")
      (node (ref "J2") (pin "H16") (pinfunction "H16_H16") (pintype "passive"))
      (node (ref "R37") (pin "2") (pinfunction "2_2") (pintype "passive"))
      (node (ref "RJ2_FCL") (pin "TP") (pinfunction "TP_TP") (pintype "input"))
    )
    (net (code "47") (name "FMC_LA12_N") (class "Default")
      (node (ref "J2") (pin "G16") (pinfunction "G16_G16") (pintype "passive"))
    )
    (net (code "48") (name "FMC_LA12_P") (class "Default")
      (node (ref "J2") (pin "G15") (pinfunction "G15_G15") (pintype "passive"))
    )
    (net (code "49") (name "FMC_LA13_N") (class "Default")
      (node (ref "J2") (pin "D18") (pinfunction "D18_D18") (pintype "passive"))
      (node (ref "JP1") (pin "13") (pinfunction "13_13") (pintype "passive"))
    )
    (net (code "50") (name "FMC_LA13_P") (class "Default")
      (node (ref "J2") (pin "D17") (pinfunction "D17_D17") (pintype "passive"))
      (node (ref "JP1") (pin "14") (pinfunction "14_14") (pintype "passive"))
    )
    (net (code "51") (name "FMC_LA14_N") (class "Default")
      (node (ref "J2") (pin "C19") (pinfunction "C19_C19") (pintype "passive"))
      (node (ref "JP1") (pin "11") (pinfunction "11_11") (pintype "passive"))
    )
    (net (code "52") (name "FMC_LA14_P") (class "Default")
      (node (ref "J2") (pin "C18") (pinfunction "C18_C18") (pintype "passive"))
      (node (ref "JP1") (pin "12") (pinfunction "12_12") (pintype "passive"))
    )
    (net (code "53") (name "FMC_LA15_N") (class "Default")
      (node (ref "J2") (pin "H20") (pinfunction "H20_H20") (pintype "passive"))
      (node (ref "U20") (pin "4") (pinfunction "A2_4") (pintype "bidirectional"))
    )
    (net (code "54") (name "FMC_LA15_P") (class "Default")
      (node (ref "J2") (pin "H19") (pinfunction "H19_H19") (pintype "passive"))
      (node (ref "RJ2_FC") (pin "TP") (pinfunction "TP_TP") (pintype "input"))
      (node (ref "U20") (pin "5") (pinfunction "A1_5") (pintype "bidirectional"))
    )
    (net (code "55") (name "FMC_LA16_N") (class "Default")
      (node (ref "J2") (pin "G19") (pinfunction "G19_G19") (pintype "passive"))
    )
    (net (code "56") (name "FMC_LA16_P") (class "Default")
      (node (ref "J2") (pin "G18") (pinfunction "G18_G18") (pintype "passive"))
    )
    (net (code "57") (name "FMC_LA17_CC_N") (class "Default")
      (node (ref "J2") (pin "D21") (pinfunction "D21_D21") (pintype "passive"))
    )
    (net (code "58") (name "FMC_LA17_CC_P") (class "Default")
      (node (ref "J2") (pin "D20") (pinfunction "D20_D20") (pintype "passive"))
    )
    (net (code "59") (name "FMC_LA18_CC_N") (class "Default")
      (node (ref "J2") (pin "C23") (pinfunction "C23_C23") (pintype "passive"))
    )
    (net (code "60") (name "FMC_LA18_CC_P") (class "Default")
      (node (ref "J2") (pin "C22") (pinfunction "C22_C22") (pintype "passive"))
    )
    (net (code "61") (name "FMC_LA19_N") (class "Default")
      (node (ref "J2") (pin "H23") (pinfunction "H23_H23") (pintype "passive"))
      (node (ref "RJ3_FC") (pin "TP") (pinfunction "TP_TP") (pintype "input"))
      (node (ref "U19") (pin "4") (pinfunction "A2_4") (pintype "bidirectional"))
    )
    (net (code "62") (name "FMC_LA19_P") (class "Default")
      (node (ref "J2") (pin "H22") (pinfunction "H22_H22") (pintype "passive"))
      (node (ref "U19") (pin "5") (pinfunction "A1_5") (pintype "bidirectional"))
    )
    (net (code "63") (name "FMC_LA20_N") (class "Default")
      (node (ref "J2") (pin "G22") (pinfunction "G22_G22") (pintype "passive"))
      (node (ref "R57") (pin "2") (pinfunction "2_2") (pintype "passive"))
    )
    (net (code "64") (name "FMC_LA20_P") (class "Default")
      (node (ref "J2") (pin "G21") (pinfunction "G21_G21") (pintype "passive"))
      (node (ref "R7") (pin "1") (pinfunction "1_1") (pintype "passive"))
      (node (ref "U17") (pin "P2") (pinfunction "RESET_P2") (pintype "bidirectional"))
    )
    (net (code "65") (name "FMC_LA21_N") (class "Default")
      (node (ref "J2") (pin "H26") (pinfunction "H26_H26") (pintype "passive"))
      (node (ref "RJ3_FDD") (pin "TP") (pinfunction "TP_TP") (pintype "input"))
      (node (ref "U8") (pin "P2") (pinfunction "DE_P2") (pintype "bidirectional"))
      (node (ref "U8") (pin "P3") (pinfunction "RE_P3") (pintype "bidirectional"))
    )
    (net (code "66") (name "FMC_LA21_P") (class "Default")
      (node (ref "J2") (pin "H25") (pinfunction "H25_H25") (pintype "passive"))
      (node (ref "R35") (pin "2") (pinfunction "2_2") (pintype "passive"))
      (node (ref "RJ3_FDA") (pin "TP") (pinfunction "TP_TP") (pintype "input"))
    )
    (net (code "67") (name "FMC_LA22_N") (class "Default")
      (node (ref "J2") (pin "G25") (pinfunction "G25_G25") (pintype "passive"))
    )
    (net (code "68") (name "FMC_LA22_P") (class "Default")
      (node (ref "J2") (pin "G24") (pinfunction "G24_G24") (pintype "passive"))
    )
    (net (code "69") (name "FMC_LA23_N") (class "Default")
      (node (ref "J2") (pin "D24") (pinfunction "D24_D24") (pintype "passive"))
      (node (ref "R65") (pin "2") (pinfunction "2_2") (pintype "passive"))
    )
    (net (code "70") (name "FMC_LA23_P") (class "Default")
      (node (ref "J2") (pin "D23") (pinfunction "D23_D23") (pintype "passive"))
      (node (ref "R66") (pin "2") (pinfunction "2_2") (pintype "passive"))
    )
    (net (code "71") (name "FMC_LA24_N") (class "Default")
      (node (ref "J2") (pin "H29") (pinfunction "H29_H29") (pintype "passive"))
      (node (ref "U6") (pin "P2") (pinfunction "DE_P2") (pintype "bidirectional"))
      (node (ref "U6") (pin "P3") (pinfunction "RE_P3") (pintype "bidirectional"))
    )
    (net (code "72") (name "FMC_LA24_P") (class "Default")
      (node (ref "J2") (pin "H28") (pinfunction "H28_H28") (pintype "passive"))
      (node (ref "R31") (pin "2") (pinfunction "2_2") (pintype "passive"))
    )
    (net (code "73") (name "FMC_LA25_N") (class "Default")
      (node (ref "J2") (pin "G28") (pinfunction "G28_G28") (pintype "passive"))
      (node (ref "RJ3_FCD") (pin "TP") (pinfunction "TP_TP") (pintype "input"))
      (node (ref "U7") (pin "P2") (pinfunction "DE_P2") (pintype "bidirectional"))
      (node (ref "U7") (pin "P3") (pinfunction "RE_P3") (pintype "bidirectional"))
    )
    (net (code "74") (name "FMC_LA25_P") (class "Default")
      (node (ref "J2") (pin "G27") (pinfunction "G27_G27") (pintype "passive"))
      (node (ref "R33") (pin "2") (pinfunction "2_2") (pintype "passive"))
      (node (ref "RJ3_FCL") (pin "TP") (pinfunction "TP_TP") (pintype "input"))
    )
    (net (code "75") (name "FMC_LA26_N") (class "Default")
      (node (ref "J2") (pin "D27") (pinfunction "D27_D27") (pintype "passive"))
    )
    (net (code "76") (name "FMC_LA26_P") (class "Default")
      (node (ref "J2") (pin "D26") (pinfunction "D26_D26") (pintype "passive"))
    )
    (net (code "77") (name "FMC_LA27_N") (class "Default")
      (node (ref "J2") (pin "C27") (pinfunction "C27_C27") (pintype "passive"))
    )
    (net (code "78") (name "FMC_LA27_P") (class "Default")
      (node (ref "J2") (pin "C26") (pinfunction "C26_C26") (pintype "passive"))
    )
    (net (code "79") (name "FMC_LA28_N") (class "Default")
      (node (ref "J2") (pin "H32") (pinfunction "H32_H32") (pintype "passive"))
      (node (ref "U5") (pin "P2") (pinfunction "DE_P2") (pintype "bidirectional"))
      (node (ref "U5") (pin "P3") (pinfunction "RE_P3") (pintype "bidirectional"))
    )
    (net (code "80") (name "FMC_LA28_P") (class "Default")
      (node (ref "J2") (pin "H31") (pinfunction "H31_H31") (pintype "passive"))
      (node (ref "R29") (pin "2") (pinfunction "2_2") (pintype "passive"))
    )
    (net (code "81") (name "FMC_LA29_N") (class "Default")
      (node (ref "J2") (pin "G31") (pinfunction "G31_G31") (pintype "passive"))
      (node (ref "U18") (pin "4") (pinfunction "A2_4") (pintype "bidirectional"))
    )
    (net (code "82") (name "FMC_LA29_P") (class "Default")
      (node (ref "J2") (pin "G30") (pinfunction "G30_G30") (pintype "passive"))
      (node (ref "R59") (pin "1") (pinfunction "1_1") (pintype "passive"))
      (node (ref "U18") (pin "5") (pinfunction "A1_5") (pintype "bidirectional"))
    )
    (net (code "83") (name "FMC_LA30_N") (class "Default")
      (node (ref "J2") (pin "H35") (pinfunction "H35_H35") (pintype "passive"))
      (node (ref "U4") (pin "P2") (pinfunction "DE_P2") (pintype "bidirectional"))
      (node (ref "U4") (pin "P3") (pinfunction "RE_P3") (pintype "bidirectional"))
    )
    (net (code "84") (name "FMC_LA30_P") (class "Default")
      (node (ref "J2") (pin "H34") (pinfunction "H34_H34") (pintype "passive"))
      (node (ref "R27") (pin "2") (pinfunction "2_2") (pintype "passive"))
    )
    (net (code "85") (name "FMC_LA31_N") (class "Default")
      (node (ref "J2") (pin "G34") (pinfunction "G34_G34") (pintype "passive"))
      (node (ref "R25") (pin "2") (pinfunction "2_2") (pintype "passive"))
    )
    (net (code "86") (name "FMC_LA31_P") (class "Default")
      (node (ref "J2") (pin "G33") (pinfunction "G33_G33") (pintype "passive"))
      (node (ref "U3") (pin "P2") (pinfunction "DE_P2") (pintype "bidirectional"))
      (node (ref "U3") (pin "P3") (pinfunction "RE_P3") (pintype "bidirectional"))
    )
    (net (code "87") (name "FMC_LA32_N") (class "Default")
      (node (ref "J2") (pin "H38") (pinfunction "H38_H38") (pintype "passive"))
      (node (ref "U2") (pin "P2") (pinfunction "DE_P2") (pintype "bidirectional"))
      (node (ref "U2") (pin "P3") (pinfunction "RE_P3") (pintype "bidirectional"))
    )
    (net (code "88") (name "FMC_LA32_P") (class "Default")
      (node (ref "J2") (pin "H37") (pinfunction "H37_H37") (pintype "passive"))
      (node (ref "R23") (pin "2") (pinfunction "2_2") (pintype "passive"))
    )
    (net (code "89") (name "FMC_LA33_N") (class "Default")
      (node (ref "J2") (pin "G37") (pinfunction "G37_G37") (pintype "passive"))
      (node (ref "U1") (pin "P2") (pinfunction "DE_P2") (pintype "bidirectional"))
      (node (ref "U1") (pin "P3") (pinfunction "RE_P3") (pintype "bidirectional"))
    )
    (net (code "90") (name "FMC_LA33_P") (class "Default")
      (node (ref "J2") (pin "G36") (pinfunction "G36_G36") (pintype "passive"))
      (node (ref "R2") (pin "2") (pinfunction "2_2") (pintype "passive"))
    )
    (net (code "91") (name "FMC_TCK") (class "Default")
      (node (ref "J2") (pin "D29") (pinfunction "D29_D29") (pintype "passive"))
    )
    (net (code "92") (name "FMC_TDI_TDO") (class "Default")
      (node (ref "J2") (pin "D30") (pinfunction "D30_D30") (pintype "passive"))
      (node (ref "J2") (pin "D31") (pinfunction "D31_D31") (pintype "passive"))
    )
    (net (code "93") (name "FMC_TMS") (class "Default")
      (node (ref "J2") (pin "D33") (pinfunction "D33_D33") (pintype "passive"))
    )
    (net (code "94") (name "GA0") (class "Default")
      (node (ref "IC1") (pin "2") (pinfunction "A1_2") (pintype "input"))
      (node (ref "J2") (pin "C34") (pinfunction "C34_C34") (pintype "passive"))
    )
    (net (code "95") (name "GA1") (class "Default")
      (node (ref "IC1") (pin "1") (pinfunction "A0_1") (pintype "input"))
      (node (ref "J2") (pin "D35") (pinfunction "D35_D35") (pintype "passive"))
    )
    (net (code "96") (name "Net-(1V8_GOOD-PadC)") (class "Default")
      (node (ref "1V8_GOOD") (pin "C") (pinfunction "C_C") (pintype "passive"))
      (node (ref "R62") (pin "1") (pinfunction "1_1") (pintype "passive"))
    )
    (net (code "97") (name "Net-(3V3_GOOD-PadC)") (class "Default")
      (node (ref "3V3_GOOD") (pin "C") (pinfunction "C_C") (pintype "passive"))
      (node (ref "R56") (pin "2") (pinfunction "2_2") (pintype "passive"))
    )
    (net (code "98") (name "Net-(5V_GOOD-PadC)") (class "Default")
      (node (ref "5V_GOOD") (pin "C") (pinfunction "C_C") (pintype "passive"))
      (node (ref "R53") (pin "2") (pinfunction "2_2") (pintype "passive"))
    )
    (net (code "99") (name "Net-(12V_GOOD-PadC)") (class "Default")
      (node (ref "12V_GOOD") (pin "C") (pinfunction "C_C") (pintype "passive"))
      (node (ref "R54") (pin "2") (pinfunction "2_2") (pintype "passive"))
    )
    (net (code "100") (name "Net-(IC1-WP)") (class "Default")
      (node (ref "IC1") (pin "7") (pinfunction "WP_7") (pintype "input"))
      (node (ref "R52") (pin "1") (pinfunction "1_1") (pintype "passive"))
    )
    (net (code "101") (name "Net-(U1-DI)") (class "Default")
      (node (ref "R2") (pin "1") (pinfunction "1_1") (pintype "passive"))
      (node (ref "U1") (pin "P1") (pinfunction "RO_P1") (pintype "bidirectional"))
      (node (ref "U1") (pin "P4") (pinfunction "DI_P4") (pintype "bidirectional"))
    )
    (net (code "102") (name "Net-(U2-DI)") (class "Default")
      (node (ref "R23") (pin "1") (pinfunction "1_1") (pintype "passive"))
      (node (ref "U2") (pin "P1") (pinfunction "RO_P1") (pintype "bidirectional"))
      (node (ref "U2") (pin "P4") (pinfunction "DI_P4") (pintype "bidirectional"))
    )
    (net (code "103") (name "Net-(U3-DI)") (class "Default")
      (node (ref "R25") (pin "1") (pinfunction "1_1") (pintype "passive"))
      (node (ref "U3") (pin "P1") (pinfunction "RO_P1") (pintype "bidirectional"))
      (node (ref "U3") (pin "P4") (pinfunction "DI_P4") (pintype "bidirectional"))
    )
    (net (code "104") (name "Net-(U4-DI)") (class "Default")
      (node (ref "R27") (pin "1") (pinfunction "1_1") (pintype "passive"))
      (node (ref "U4") (pin "P1") (pinfunction "RO_P1") (pintype "bidirectional"))
      (node (ref "U4") (pin "P4") (pinfunction "DI_P4") (pintype "bidirectional"))
    )
    (net (code "105") (name "Net-(U5-DI)") (class "Default")
      (node (ref "R29") (pin "1") (pinfunction "1_1") (pintype "passive"))
      (node (ref "U5") (pin "P1") (pinfunction "RO_P1") (pintype "bidirectional"))
      (node (ref "U5") (pin "P4") (pinfunction "DI_P4") (pintype "bidirectional"))
    )
    (net (code "106") (name "Net-(U6-DI)") (class "Default")
      (node (ref "R31") (pin "1") (pinfunction "1_1") (pintype "passive"))
      (node (ref "U6") (pin "P1") (pinfunction "RO_P1") (pintype "bidirectional"))
      (node (ref "U6") (pin "P4") (pinfunction "DI_P4") (pintype "bidirectional"))
    )
    (net (code "107") (name "Net-(U7-DI)") (class "Default")
      (node (ref "R33") (pin "1") (pinfunction "1_1") (pintype "passive"))
      (node (ref "U7") (pin "P1") (pinfunction "RO_P1") (pintype "bidirectional"))
      (node (ref "U7") (pin "P4") (pinfunction "DI_P4") (pintype "bidirectional"))
    )
    (net (code "108") (name "Net-(U8-DI)") (class "Default")
      (node (ref "R35") (pin "1") (pinfunction "1_1") (pintype "passive"))
      (node (ref "U8") (pin "P1") (pinfunction "RO_P1") (pintype "bidirectional"))
      (node (ref "U8") (pin "P4") (pinfunction "DI_P4") (pintype "bidirectional"))
    )
    (net (code "109") (name "Net-(U9-DI)") (class "Default")
      (node (ref "R37") (pin "1") (pinfunction "1_1") (pintype "passive"))
      (node (ref "U9") (pin "P1") (pinfunction "RO_P1") (pintype "bidirectional"))
      (node (ref "U9") (pin "P4") (pinfunction "DI_P4") (pintype "bidirectional"))
    )
    (net (code "110") (name "Net-(U10-DI)") (class "Default")
      (node (ref "R39") (pin "1") (pinfunction "1_1") (pintype "passive"))
      (node (ref "U10") (pin "P1") (pinfunction "RO_P1") (pintype "bidirectional"))
      (node (ref "U10") (pin "P4") (pinfunction "DI_P4") (pintype "bidirectional"))
    )
    (net (code "111") (name "Net-(U11-DI)") (class "Default")
      (node (ref "R41") (pin "1") (pinfunction "1_1") (pintype "passive"))
      (node (ref "U11") (pin "P1") (pinfunction "RO_P1") (pintype "bidirectional"))
      (node (ref "U11") (pin "P4") (pinfunction "DI_P4") (pintype "bidirectional"))
    )
    (net (code "112") (name "Net-(U12-DI)") (class "Default")
      (node (ref "R43") (pin "1") (pinfunction "1_1") (pintype "passive"))
      (node (ref "U12") (pin "P1") (pinfunction "RO_P1") (pintype "bidirectional"))
      (node (ref "U12") (pin "P4") (pinfunction "DI_P4") (pintype "bidirectional"))
    )
    (net (code "113") (name "Net-(U13-DI)") (class "Default")
      (node (ref "R45") (pin "1") (pinfunction "1_1") (pintype "passive"))
      (node (ref "U13") (pin "P1") (pinfunction "RO_P1") (pintype "bidirectional"))
      (node (ref "U13") (pin "P4") (pinfunction "DI_P4") (pintype "bidirectional"))
    )
    (net (code "114") (name "Net-(U14-DI)") (class "Default")
      (node (ref "R47") (pin "1") (pinfunction "1_1") (pintype "passive"))
      (node (ref "U14") (pin "P1") (pinfunction "RO_P1") (pintype "bidirectional"))
      (node (ref "U14") (pin "P4") (pinfunction "DI_P4") (pintype "bidirectional"))
    )
    (net (code "115") (name "Net-(U15-DI)") (class "Default")
      (node (ref "R49") (pin "1") (pinfunction "1_1") (pintype "passive"))
      (node (ref "U15") (pin "P1") (pinfunction "RO_P1") (pintype "bidirectional"))
      (node (ref "U15") (pin "P4") (pinfunction "DI_P4") (pintype "bidirectional"))
    )
    (net (code "116") (name "Net-(U16-DI)") (class "Default")
      (node (ref "R51") (pin "1") (pinfunction "1_1") (pintype "passive"))
      (node (ref "U16") (pin "P1") (pinfunction "RO_P1") (pintype "bidirectional"))
      (node (ref "U16") (pin "P4") (pinfunction "DI_P4") (pintype "bidirectional"))
    )
    (net (code "117") (name "Net-(U17-SCL)") (class "Default")
      (node (ref "MSCL") (pin "TP") (pinfunction "TP_TP") (pintype "input"))
      (node (ref "R6") (pin "1") (pinfunction "1_1") (pintype "passive"))
      (node (ref "R64") (pin "2") (pinfunction "2_2") (pintype "passive"))
      (node (ref "R66") (pin "1") (pinfunction "1_1") (pintype "passive"))
      (node (ref "U17") (pin "P21") (pinfunction "SCL_P21") (pintype "bidirectional"))
    )
    (net (code "118") (name "Net-(U17-SDA)") (class "Default")
      (node (ref "MSDA") (pin "TP") (pinfunction "TP_TP") (pintype "input"))
      (node (ref "R5") (pin "1") (pinfunction "1_1") (pintype "passive"))
      (node (ref "R63") (pin "2") (pinfunction "2_2") (pintype "passive"))
      (node (ref "R65") (pin "1") (pinfunction "1_1") (pintype "passive"))
      (node (ref "U17") (pin "P22") (pinfunction "SDA_P22") (pintype "bidirectional"))
    )
    (net (code "119") (name "Net-(U40-D)") (class "Default")
      (node (ref "R62") (pin "2") (pinfunction "2_2") (pintype "passive"))
      (node (ref "U40") (pin "P3") (pinfunction "D_P3") (pintype "passive"))
    )
    (net (code "120") (name "Net-(U40-G)") (class "Default")
      (node (ref "R60") (pin "1") (pinfunction "1_1") (pintype "passive"))
      (node (ref "R61") (pin "1") (pinfunction "1_1") (pintype "passive"))
      (node (ref "U40") (pin "P1") (pinfunction "G_P1") (pintype "passive"))
    )
    (net (code "121") (name "RJ1_CLK_N") (class "Default")
      (node (ref "J1") (pin "1.2") (pinfunction "1.2_1.2") (pintype "passive"))
      (node (ref "R44") (pin "2") (pinfunction "2_2") (pintype "passive"))
      (node (ref "RJ1_CL-") (pin "TP") (pinfunction "TP_TP") (pintype "input"))
      (node (ref "U13") (pin "P8") (pinfunction "B_P8") (pintype "bidirectional"))
    )
    (net (code "122") (name "RJ1_CLK_P") (class "Default")
      (node (ref "J1") (pin "1.1") (pinfunction "1.1_1.1") (pintype "passive"))
      (node (ref "R44") (pin "1") (pinfunction "1_1") (pintype "passive"))
      (node (ref "RJ1_CL+") (pin "TP") (pinfunction "TP_TP") (pintype "input"))
      (node (ref "U13") (pin "P7") (pinfunction "A_P7") (pintype "bidirectional"))
    )
    (net (code "123") (name "RJ1_CONV") (class "Default")
      (node (ref "J1") (pin "1.5") (pinfunction "1.5_1.5") (pintype "passive"))
      (node (ref "RJ1_CONV") (pin "TP") (pinfunction "TP_TP") (pintype "input"))
      (node (ref "U21") (pin "8") (pinfunction "B1_8") (pintype "bidirectional"))
    )
    (net (code "124") (name "RJ1_DATA_N") (class "Default")
      (node (ref "J1") (pin "1.3") (pinfunction "1.3_1.3") (pintype "passive"))
      (node (ref "R46") (pin "2") (pinfunction "2_2") (pintype "passive"))
      (node (ref "RJ1_FDA-") (pin "TP") (pinfunction "TP_TP") (pintype "input"))
      (node (ref "U14") (pin "P8") (pinfunction "B_P8") (pintype "bidirectional"))
    )
    (net (code "125") (name "RJ1_DATA_P") (class "Default")
      (node (ref "J1") (pin "1.6") (pinfunction "1.6_1.6") (pintype "passive"))
      (node (ref "R46") (pin "1") (pinfunction "1_1") (pintype "passive"))
      (node (ref "RJ1_FDA+") (pin "TP") (pinfunction "TP_TP") (pintype "input"))
      (node (ref "U14") (pin "P7") (pinfunction "A_P7") (pintype "bidirectional"))
    )
    (net (code "126") (name "RJ1_SCL") (class "Default")
      (node (ref "J1") (pin "1.7") (pinfunction "1.7_1.7") (pintype "passive"))
      (node (ref "R17") (pin "1") (pinfunction "1_1") (pintype "passive"))
      (node (ref "RJ1_SCL") (pin "TP") (pinfunction "TP_TP") (pintype "input"))
      (node (ref "U17") (pin "P15") (pinfunction "SC5_P15") (pintype "bidirectional"))
    )
    (net (code "127") (name "RJ1_SDO") (class "Default")
      (node (ref "J1") (pin "1.8") (pinfunction "1.8_1.8") (pintype "passive"))
      (node (ref "R16") (pin "1") (pinfunction "1_1") (pintype "passive"))
      (node (ref "RJ1_SDO") (pin "TP") (pinfunction "TP_TP") (pintype "input"))
      (node (ref "U17") (pin "P14") (pinfunction "SD5_P14") (pintype "bidirectional"))
    )
    (net (code "128") (name "RJ2_CLK_N") (class "Default")
      (node (ref "J1") (pin "2.2") (pinfunction "2.2_2.2") (pintype "passive"))
      (node (ref "R36") (pin "2") (pinfunction "2_2") (pintype "passive"))
      (node (ref "RJ2_FCL-") (pin "TP") (pinfunction "TP_TP") (pintype "input"))
      (node (ref "U9") (pin "P8") (pinfunction "B_P8") (pintype "bidirectional"))
    )
    (net (code "129") (name "RJ2_CLK_P") (class "Default")
      (node (ref "J1") (pin "2.1") (pinfunction "2.1_2.1") (pintype "passive"))
      (node (ref "R36") (pin "1") (pinfunction "1_1") (pintype "passive"))
      (node (ref "RJ2_FCL+") (pin "TP") (pinfunction "TP_TP") (pintype "input"))
      (node (ref "U9") (pin "P7") (pinfunction "A_P7") (pintype "bidirectional"))
    )
    (net (code "130") (name "RJ2_CONV") (class "Default")
      (node (ref "J1") (pin "2.5") (pinfunction "2.5_2.5") (pintype "passive"))
      (node (ref "RJ2_CONV") (pin "TP") (pinfunction "TP_TP") (pintype "input"))
      (node (ref "U20") (pin "8") (pinfunction "B1_8") (pintype "bidirectional"))
    )
    (net (code "131") (name "RJ2_DATA_N") (class "Default")
      (node (ref "J1") (pin "2.3") (pinfunction "2.3_2.3") (pintype "passive"))
      (node (ref "R38") (pin "2") (pinfunction "2_2") (pintype "passive"))
      (node (ref "RJ2_FDA-") (pin "TP") (pinfunction "TP_TP") (pintype "input"))
      (node (ref "U10") (pin "P8") (pinfunction "B_P8") (pintype "bidirectional"))
    )
    (net (code "132") (name "RJ2_DATA_P") (class "Default")
      (node (ref "J1") (pin "2.6") (pinfunction "2.6_2.6") (pintype "passive"))
      (node (ref "R38") (pin "1") (pinfunction "1_1") (pintype "passive"))
      (node (ref "RJ2_FDA+") (pin "TP") (pinfunction "TP_TP") (pintype "input"))
      (node (ref "U10") (pin "P7") (pinfunction "A_P7") (pintype "bidirectional"))
    )
    (net (code "133") (name "RJ2_SCL") (class "Default")
      (node (ref "J1") (pin "2.7") (pinfunction "2.7_2.7") (pintype "passive"))
      (node (ref "R21") (pin "1") (pinfunction "1_1") (pintype "passive"))
      (node (ref "RJ2_SCL") (pin "TP") (pinfunction "TP_TP") (pintype "input"))
      (node (ref "U17") (pin "P19") (pinfunction "SC7_P19") (pintype "bidirectional"))
    )
    (net (code "134") (name "RJ2_SDO") (class "Default")
      (node (ref "J1") (pin "2.8") (pinfunction "2.8_2.8") (pintype "passive"))
      (node (ref "R20") (pin "1") (pinfunction "1_1") (pintype "passive"))
      (node (ref "RJ2_SDO") (pin "TP") (pinfunction "TP_TP") (pintype "input"))
      (node (ref "U17") (pin "P18") (pinfunction "SD7_P18") (pintype "bidirectional"))
    )
    (net (code "135") (name "RJ3_CLK_N") (class "Default")
      (node (ref "J1") (pin "3.2") (pinfunction "3.2_3.2") (pintype "passive"))
      (node (ref "R32") (pin "2") (pinfunction "2_2") (pintype "passive"))
      (node (ref "RJ3_FCL-") (pin "TP") (pinfunction "TP_TP") (pintype "input"))
      (node (ref "U7") (pin "P8") (pinfunction "B_P8") (pintype "bidirectional"))
    )
    (net (code "136") (name "RJ3_CLK_P") (class "Default")
      (node (ref "J1") (pin "3.1") (pinfunction "3.1_3.1") (pintype "passive"))
      (node (ref "R32") (pin "1") (pinfunction "1_1") (pintype "passive"))
      (node (ref "RJ3_FCL+") (pin "TP") (pinfunction "TP_TP") (pintype "input"))
      (node (ref "U7") (pin "P7") (pinfunction "A_P7") (pintype "bidirectional"))
    )
    (net (code "137") (name "RJ3_CONV") (class "Default")
      (node (ref "J1") (pin "3.5") (pinfunction "3.5_3.5") (pintype "passive"))
      (node (ref "RJ3_CONV") (pin "TP") (pinfunction "TP_TP") (pintype "input"))
      (node (ref "U19") (pin "1") (pinfunction "B2_1") (pintype "bidirectional"))
    )
    (net (code "138") (name "RJ3_DATA_N") (class "Default")
      (node (ref "J1") (pin "3.3") (pinfunction "3.3_3.3") (pintype "passive"))
      (node (ref "R34") (pin "2") (pinfunction "2_2") (pintype "passive"))
      (node (ref "RJ3_FDA-") (pin "TP") (pinfunction "TP_TP") (pintype "input"))
      (node (ref "U8") (pin "P8") (pinfunction "B_P8") (pintype "bidirectional"))
    )
    (net (code "139") (name "RJ3_DATA_P") (class "Default")
      (node (ref "J1") (pin "3.6") (pinfunction "3.6_3.6") (pintype "passive"))
      (node (ref "R34") (pin "1") (pinfunction "1_1") (pintype "passive"))
      (node (ref "RJ3_FDA+") (pin "TP") (pinfunction "TP_TP") (pintype "input"))
      (node (ref "U8") (pin "P7") (pinfunction "A_P7") (pintype "bidirectional"))
    )
    (net (code "140") (name "RJ3_SCL") (class "Default")
      (node (ref "J1") (pin "3.7") (pinfunction "3.7_3.7") (pintype "passive"))
      (node (ref "R9") (pin "1") (pinfunction "1_1") (pintype "passive"))
      (node (ref "RJ3_SCL") (pin "TP") (pinfunction "TP_TP") (pintype "input"))
      (node (ref "U17") (pin "P6") (pinfunction "SC1_P6") (pintype "bidirectional"))
    )
    (net (code "141") (name "RJ3_SDO") (class "Default")
      (node (ref "J1") (pin "3.8") (pinfunction "3.8_3.8") (pintype "passive"))
      (node (ref "R8") (pin "1") (pinfunction "1_1") (pintype "passive"))
      (node (ref "RJ3_SDO") (pin "TP") (pinfunction "TP_TP") (pintype "input"))
      (node (ref "U17") (pin "P5") (pinfunction "SD1_P5") (pintype "bidirectional"))
    )
    (net (code "142") (name "RJ4_CLK_N") (class "Default")
      (node (ref "J1") (pin "4.2") (pinfunction "4.2_4.2") (pintype "passive"))
      (node (ref "R24") (pin "2") (pinfunction "2_2") (pintype "passive"))
      (node (ref "U3") (pin "P8") (pinfunction "B_P8") (pintype "bidirectional"))
    )
    (net (code "143") (name "RJ4_CLK_P") (class "Default")
      (node (ref "J1") (pin "4.1") (pinfunction "4.1_4.1") (pintype "passive"))
      (node (ref "R24") (pin "1") (pinfunction "1_1") (pintype "passive"))
      (node (ref "U3") (pin "P7") (pinfunction "A_P7") (pintype "bidirectional"))
    )
    (net (code "144") (name "RJ4_CONV") (class "Default")
      (node (ref "J1") (pin "4.5") (pinfunction "4.5_4.5") (pintype "passive"))
      (node (ref "U18") (pin "1") (pinfunction "B2_1") (pintype "bidirectional"))
    )
    (net (code "145") (name "RJ4_DATA_N") (class "Default")
      (node (ref "J1") (pin "4.3") (pinfunction "4.3_4.3") (pintype "passive"))
      (node (ref "R26") (pin "2") (pinfunction "2_2") (pintype "passive"))
      (node (ref "U4") (pin "P8") (pinfunction "B_P8") (pintype "bidirectional"))
    )
    (net (code "146") (name "RJ4_DATA_P") (class "Default")
      (node (ref "J1") (pin "4.6") (pinfunction "4.6_4.6") (pintype "passive"))
      (node (ref "R26") (pin "1") (pinfunction "1_1") (pintype "passive"))
      (node (ref "U4") (pin "P7") (pinfunction "A_P7") (pintype "bidirectional"))
    )
    (net (code "147") (name "RJ4_SCL") (class "Default")
      (node (ref "J1") (pin "4.7") (pinfunction "4.7_4.7") (pintype "passive"))
      (node (ref "R13") (pin "1") (pinfunction "1_1") (pintype "passive"))
      (node (ref "U17") (pin "P10") (pinfunction "SC3_P10") (pintype "bidirectional"))
    )
    (net (code "148") (name "RJ4_SDO") (class "Default")
      (node (ref "J1") (pin "4.8") (pinfunction "4.8_4.8") (pintype "passive"))
      (node (ref "R12") (pin "1") (pinfunction "1_1") (pintype "passive"))
      (node (ref "U17") (pin "P9") (pinfunction "SD3_P9") (pintype "bidirectional"))
    )
    (net (code "149") (name "RJ5_CLK_N") (class "Default")
      (node (ref "J1") (pin "5.7") (pinfunction "5.2_5.7") (pintype "passive"))
      (node (ref "R48") (pin "2") (pinfunction "2_2") (pintype "passive"))
      (node (ref "U15") (pin "P8") (pinfunction "B_P8") (pintype "bidirectional"))
    )
    (net (code "150") (name "RJ5_CLK_P") (class "Default")
      (node (ref "J1") (pin "5.8") (pinfunction "5.1_5.8") (pintype "passive"))
      (node (ref "R48") (pin "1") (pinfunction "1_1") (pintype "passive"))
      (node (ref "U15") (pin "P7") (pinfunction "A_P7") (pintype "bidirectional"))
    )
    (net (code "151") (name "RJ5_CONV") (class "Default")
      (node (ref "J1") (pin "5.4") (pinfunction "5.5_5.4") (pintype "passive"))
      (node (ref "U21") (pin "1") (pinfunction "B2_1") (pintype "bidirectional"))
    )
    (net (code "152") (name "RJ5_DATA_N") (class "Default")
      (node (ref "J1") (pin "5.6") (pinfunction "5.3_5.6") (pintype "passive"))
      (node (ref "R50") (pin "2") (pinfunction "2_2") (pintype "passive"))
      (node (ref "U16") (pin "P8") (pinfunction "B_P8") (pintype "bidirectional"))
    )
    (net (code "153") (name "RJ5_DATA_P") (class "Default")
      (node (ref "J1") (pin "5.3") (pinfunction "5.6_5.3") (pintype "passive"))
      (node (ref "R50") (pin "1") (pinfunction "1_1") (pintype "passive"))
      (node (ref "U16") (pin "P7") (pinfunction "A_P7") (pintype "bidirectional"))
    )
    (net (code "154") (name "RJ5_SCL") (class "Default")
      (node (ref "J1") (pin "5.2") (pinfunction "5.7_5.2") (pintype "passive"))
      (node (ref "R15") (pin "1") (pinfunction "1_1") (pintype "passive"))
      (node (ref "U17") (pin "P13") (pinfunction "SC4_P13") (pintype "bidirectional"))
    )
    (net (code "155") (name "RJ5_SDO") (class "Default")
      (node (ref "J1") (pin "5.1") (pinfunction "5.8_5.1") (pintype "passive"))
      (node (ref "R14") (pin "1") (pinfunction "1_1") (pintype "passive"))
      (node (ref "U17") (pin "P12") (pinfunction "SD4_P12") (pintype "bidirectional"))
    )
    (net (code "156") (name "RJ6_CLK_N") (class "Default")
      (node (ref "J1") (pin "6.7") (pinfunction "6.2_6.7") (pintype "passive"))
      (node (ref "R40") (pin "2") (pinfunction "2_2") (pintype "passive"))
      (node (ref "U11") (pin "P8") (pinfunction "B_P8") (pintype "bidirectional"))
    )
    (net (code "157") (name "RJ6_CLK_P") (class "Default")
      (node (ref "J1") (pin "6.8") (pinfunction "6.1_6.8") (pintype "passive"))
      (node (ref "R40") (pin "1") (pinfunction "1_1") (pintype "passive"))
      (node (ref "U11") (pin "P7") (pinfunction "A_P7") (pintype "bidirectional"))
    )
    (net (code "158") (name "RJ6_CONV") (class "Default")
      (node (ref "J1") (pin "6.4") (pinfunction "6.5_6.4") (pintype "passive"))
      (node (ref "U20") (pin "1") (pinfunction "B2_1") (pintype "bidirectional"))
    )
    (net (code "159") (name "RJ6_DATA_N") (class "Default")
      (node (ref "J1") (pin "6.6") (pinfunction "6.3_6.6") (pintype "passive"))
      (node (ref "R42") (pin "2") (pinfunction "2_2") (pintype "passive"))
      (node (ref "U12") (pin "P8") (pinfunction "B_P8") (pintype "bidirectional"))
    )
    (net (code "160") (name "RJ6_DATA_P") (class "Default")
      (node (ref "J1") (pin "6.3") (pinfunction "6.6_6.3") (pintype "passive"))
      (node (ref "R42") (pin "1") (pinfunction "1_1") (pintype "passive"))
      (node (ref "U12") (pin "P7") (pinfunction "A_P7") (pintype "bidirectional"))
    )
    (net (code "161") (name "RJ6_SCL") (class "Default")
      (node (ref "J1") (pin "6.2") (pinfunction "6.7_6.2") (pintype "passive"))
      (node (ref "R19") (pin "1") (pinfunction "1_1") (pintype "passive"))
      (node (ref "U17") (pin "P17") (pinfunction "SC6_P17") (pintype "bidirectional"))
    )
    (net (code "162") (name "RJ6_SDO") (class "Default")
      (node (ref "J1") (pin "6.1") (pinfunction "6.8_6.1") (pintype "passive"))
      (node (ref "R18") (pin "1") (pinfunction "1_1") (pintype "passive"))
      (node (ref "U17") (pin "P16") (pinfunction "SD6_P16") (pintype "bidirectional"))
    )
    (net (code "163") (name "RJ7_CLK_N") (class "Default")
      (node (ref "J1") (pin "7.7") (pinfunction "7.2_7.7") (pintype "passive"))
      (node (ref "R28") (pin "2") (pinfunction "2_2") (pintype "passive"))
      (node (ref "U5") (pin "P8") (pinfunction "B_P8") (pintype "bidirectional"))
    )
    (net (code "164") (name "RJ7_CLK_P") (class "Default")
      (node (ref "J1") (pin "7.8") (pinfunction "7.1_7.8") (pintype "passive"))
      (node (ref "R28") (pin "1") (pinfunction "1_1") (pintype "passive"))
      (node (ref "U5") (pin "P7") (pinfunction "A_P7") (pintype "bidirectional"))
    )
    (net (code "165") (name "RJ7_CONV") (class "Default")
      (node (ref "J1") (pin "7.4") (pinfunction "7.5_7.4") (pintype "passive"))
      (node (ref "U19") (pin "8") (pinfunction "B1_8") (pintype "bidirectional"))
    )
    (net (code "166") (name "RJ7_DATA_N") (class "Default")
      (node (ref "J1") (pin "7.6") (pinfunction "7.3_7.6") (pintype "passive"))
      (node (ref "R30") (pin "2") (pinfunction "2_2") (pintype "passive"))
      (node (ref "U6") (pin "P8") (pinfunction "B_P8") (pintype "bidirectional"))
    )
    (net (code "167") (name "RJ7_DATA_P") (class "Default")
      (node (ref "J1") (pin "7.3") (pinfunction "7.6_7.3") (pintype "passive"))
      (node (ref "R30") (pin "1") (pinfunction "1_1") (pintype "passive"))
      (node (ref "U6") (pin "P7") (pinfunction "A_P7") (pintype "bidirectional"))
    )
    (net (code "168") (name "RJ7_SCL") (class "Default")
      (node (ref "J1") (pin "7.2") (pinfunction "7.7_7.2") (pintype "passive"))
      (node (ref "R4") (pin "1") (pinfunction "1_1") (pintype "passive"))
      (node (ref "U17") (pin "P4") (pinfunction "SC0_P4") (pintype "bidirectional"))
    )
    (net (code "169") (name "RJ7_SDO") (class "Default")
      (node (ref "J1") (pin "7.1") (pinfunction "7.8_7.1") (pintype "passive"))
      (node (ref "R3") (pin "1") (pinfunction "1_1") (pintype "passive"))
      (node (ref "U17") (pin "P3") (pinfunction "SD0_P3") (pintype "bidirectional"))
    )
    (net (code "170") (name "RJ8_CLK_N") (class "Default")
      (node (ref "J1") (pin "8.7") (pinfunction "8.2_8.7") (pintype "passive"))
      (node (ref "R1") (pin "2") (pinfunction "2_2") (pintype "passive"))
      (node (ref "U1") (pin "P8") (pinfunction "B_P8") (pintype "bidirectional"))
    )
    (net (code "171") (name "RJ8_CLK_P") (class "Default")
      (node (ref "J1") (pin "8.8") (pinfunction "8.1_8.8") (pintype "passive"))
      (node (ref "R1") (pin "1") (pinfunction "1_1") (pintype "passive"))
      (node (ref "U1") (pin "P7") (pinfunction "A_P7") (pintype "bidirectional"))
    )
    (net (code "172") (name "RJ8_CONV") (class "Default")
      (node (ref "J1") (pin "8.4") (pinfunction "8.5_8.4") (pintype "passive"))
      (node (ref "U18") (pin "8") (pinfunction "B1_8") (pintype "bidirectional"))
    )
    (net (code "173") (name "RJ8_DATA_N") (class "Default")
      (node (ref "J1") (pin "8.6") (pinfunction "8.3_8.6") (pintype "passive"))
      (node (ref "R22") (pin "2") (pinfunction "2_2") (pintype "passive"))
      (node (ref "U2") (pin "P8") (pinfunction "B_P8") (pintype "bidirectional"))
    )
    (net (code "174") (name "RJ8_DATA_P") (class "Default")
      (node (ref "J1") (pin "8.3") (pinfunction "8.6_8.3") (pintype "passive"))
      (node (ref "R22") (pin "1") (pinfunction "1_1") (pintype "passive"))
      (node (ref "U2") (pin "P7") (pinfunction "A_P7") (pintype "bidirectional"))
    )
    (net (code "175") (name "RJ8_SCL") (class "Default")
      (node (ref "J1") (pin "8.2") (pinfunction "8.7_8.2") (pintype "passive"))
      (node (ref "R11") (pin "1") (pinfunction "1_1") (pintype "passive"))
      (node (ref "U17") (pin "P8") (pinfunction "SC2_P8") (pintype "bidirectional"))
    )
    (net (code "176") (name "RJ8_SDO") (class "Default")
      (node (ref "J1") (pin "8.1") (pinfunction "8.8_8.1") (pintype "passive"))
      (node (ref "R10") (pin "1") (pinfunction "1_1") (pintype "passive"))
      (node (ref "U17") (pin "P7") (pinfunction "SD2_P7") (pintype "bidirectional"))
    )
    (net (code "177") (name "V+") (class "Default")
      (node (ref "C35") (pin "2") (pinfunction "2_2") (pintype "passive"))
      (node (ref "J2") (pin "E39") (pinfunction "E39_E39") (pintype "passive"))
      (node (ref "J2") (pin "F40") (pinfunction "F40_F40") (pintype "passive"))
      (node (ref "J2") (pin "G39") (pinfunction "G39_G39") (pintype "passive"))
      (node (ref "J2") (pin "H40") (pinfunction "H40_H40") (pintype "passive"))
      (node (ref "JP1") (pin "2") (pinfunction "2_2") (pintype "passive"))
    )
    (net (code "178") (name "unconnected-(J2-PadA2)") (class "Default")
      (node (ref "J2") (pin "A2") (pinfunction "A2_A2") (pintype "passive"))
    )
    (net (code "179") (name "unconnected-(J2-PadA3)") (class "Default")
      (node (ref "J2") (pin "A3") (pinfunction "A3_A3") (pintype "passive"))
    )
    (net (code "180") (name "unconnected-(J2-PadA6)") (class "Default")
      (node (ref "J2") (pin "A6") (pinfunction "A6_A6") (pintype "passive"))
    )
    (net (code "181") (name "unconnected-(J2-PadA7)") (class "Default")
      (node (ref "J2") (pin "A7") (pinfunction "A7_A7") (pintype "passive"))
    )
    (net (code "182") (name "unconnected-(J2-PadA10)") (class "Default")
      (node (ref "J2") (pin "A10") (pinfunction "A10_A10") (pintype "passive"))
    )
    (net (code "183") (name "unconnected-(J2-PadA11)") (class "Default")
      (node (ref "J2") (pin "A11") (pinfunction "A11_A11") (pintype "passive"))
    )
    (net (code "184") (name "unconnected-(J2-PadA14)") (class "Default")
      (node (ref "J2") (pin "A14") (pinfunction "A14_A14") (pintype "passive"))
    )
    (net (code "185") (name "unconnected-(J2-PadA15)") (class "Default")
      (node (ref "J2") (pin "A15") (pinfunction "A15_A15") (pintype "passive"))
    )
    (net (code "186") (name "unconnected-(J2-PadA18)") (class "Default")
      (node (ref "J2") (pin "A18") (pinfunction "A18_A18") (pintype "passive"))
    )
    (net (code "187") (name "unconnected-(J2-PadA19)") (class "Default")
      (node (ref "J2") (pin "A19") (pinfunction "A19_A19") (pintype "passive"))
    )
    (net (code "188") (name "unconnected-(J2-PadA22)") (class "Default")
      (node (ref "J2") (pin "A22") (pinfunction "A22_A22") (pintype "passive"))
    )
    (net (code "189") (name "unconnected-(J2-PadA23)") (class "Default")
      (node (ref "J2") (pin "A23") (pinfunction "A23_A23") (pintype "passive"))
    )
    (net (code "190") (name "unconnected-(J2-PadA26)") (class "Default")
      (node (ref "J2") (pin "A26") (pinfunction "A26_A26") (pintype "passive"))
    )
    (net (code "191") (name "unconnected-(J2-PadA27)") (class "Default")
      (node (ref "J2") (pin "A27") (pinfunction "A27_A27") (pintype "passive"))
    )
    (net (code "192") (name "unconnected-(J2-PadA30)") (class "Default")
      (node (ref "J2") (pin "A30") (pinfunction "A30_A30") (pintype "passive"))
    )
    (net (code "193") (name "unconnected-(J2-PadA31)") (class "Default")
      (node (ref "J2") (pin "A31") (pinfunction "A31_A31") (pintype "passive"))
    )
    (net (code "194") (name "unconnected-(J2-PadA34)") (class "Default")
      (node (ref "J2") (pin "A34") (pinfunction "A34_A34") (pintype "passive"))
    )
    (net (code "195") (name "unconnected-(J2-PadA35)") (class "Default")
      (node (ref "J2") (pin "A35") (pinfunction "A35_A35") (pintype "passive"))
    )
    (net (code "196") (name "unconnected-(J2-PadA38)") (class "Default")
      (node (ref "J2") (pin "A38") (pinfunction "A38_A38") (pintype "passive"))
    )
    (net (code "197") (name "unconnected-(J2-PadA39)") (class "Default")
      (node (ref "J2") (pin "A39") (pinfunction "A39_A39") (pintype "passive"))
    )
    (net (code "198") (name "unconnected-(J2-PadB4)") (class "Default")
      (node (ref "J2") (pin "B4") (pinfunction "B4_B4") (pintype "passive"))
    )
    (net (code "199") (name "unconnected-(J2-PadB5)") (class "Default")
      (node (ref "J2") (pin "B5") (pinfunction "B5_B5") (pintype "passive"))
    )
    (net (code "200") (name "unconnected-(J2-PadB8)") (class "Default")
      (node (ref "J2") (pin "B8") (pinfunction "B8_B8") (pintype "passive"))
    )
    (net (code "201") (name "unconnected-(J2-PadB9)") (class "Default")
      (node (ref "J2") (pin "B9") (pinfunction "B9_B9") (pintype "passive"))
    )
    (net (code "202") (name "unconnected-(J2-PadB12)") (class "Default")
      (node (ref "J2") (pin "B12") (pinfunction "B12_B12") (pintype "passive"))
    )
    (net (code "203") (name "unconnected-(J2-PadB13)") (class "Default")
      (node (ref "J2") (pin "B13") (pinfunction "B13_B13") (pintype "passive"))
    )
    (net (code "204") (name "unconnected-(J2-PadB16)") (class "Default")
      (node (ref "J2") (pin "B16") (pinfunction "B16_B16") (pintype "passive"))
    )
    (net (code "205") (name "unconnected-(J2-PadB17)") (class "Default")
      (node (ref "J2") (pin "B17") (pinfunction "B17_B17") (pintype "passive"))
    )
    (net (code "206") (name "unconnected-(J2-PadB20)") (class "Default")
      (node (ref "J2") (pin "B20") (pinfunction "B20_B20") (pintype "passive"))
    )
    (net (code "207") (name "unconnected-(J2-PadB21)") (class "Default")
      (node (ref "J2") (pin "B21") (pinfunction "B21_B21") (pintype "passive"))
    )
    (net (code "208") (name "unconnected-(J2-PadB24)") (class "Default")
      (node (ref "J2") (pin "B24") (pinfunction "B24_B24") (pintype "passive"))
    )
    (net (code "209") (name "unconnected-(J2-PadB25)") (class "Default")
      (node (ref "J2") (pin "B25") (pinfunction "B25_B25") (pintype "passive"))
    )
    (net (code "210") (name "unconnected-(J2-PadB28)") (class "Default")
      (node (ref "J2") (pin "B28") (pinfunction "B28_B28") (pintype "passive"))
    )
    (net (code "211") (name "unconnected-(J2-PadB29)") (class "Default")
      (node (ref "J2") (pin "B29") (pinfunction "B29_B29") (pintype "passive"))
    )
    (net (code "212") (name "unconnected-(J2-PadB32)") (class "Default")
      (node (ref "J2") (pin "B32") (pinfunction "B32_B32") (pintype "passive"))
    )
    (net (code "213") (name "unconnected-(J2-PadB33)") (class "Default")
      (node (ref "J2") (pin "B33") (pinfunction "B33_B33") (pintype "passive"))
    )
    (net (code "214") (name "unconnected-(J2-PadB36)") (class "Default")
      (node (ref "J2") (pin "B36") (pinfunction "B36_B36") (pintype "passive"))
    )
    (net (code "215") (name "unconnected-(J2-PadB37)") (class "Default")
      (node (ref "J2") (pin "B37") (pinfunction "B37_B37") (pintype "passive"))
    )
    (net (code "216") (name "unconnected-(J2-PadD34)") (class "Default")
      (node (ref "J2") (pin "D34") (pinfunction "D34_D34") (pintype "passive"))
    )
    (net (code "217") (name "unconnected-(J2-PadE2)") (class "Default")
      (node (ref "J2") (pin "E2") (pinfunction "E2_E2") (pintype "passive"))
    )
    (net (code "218") (name "unconnected-(J2-PadE3)") (class "Default")
      (node (ref "J2") (pin "E3") (pinfunction "E3_E3") (pintype "passive"))
    )
    (net (code "219") (name "unconnected-(J2-PadE6)") (class "Default")
      (node (ref "J2") (pin "E6") (pinfunction "E6_E6") (pintype "passive"))
    )
    (net (code "220") (name "unconnected-(J2-PadE7)") (class "Default")
      (node (ref "J2") (pin "E7") (pinfunction "E7_E7") (pintype "passive"))
    )
    (net (code "221") (name "unconnected-(J2-PadE9)") (class "Default")
      (node (ref "J2") (pin "E9") (pinfunction "E9_E9") (pintype "passive"))
    )
    (net (code "222") (name "unconnected-(J2-PadE10)") (class "Default")
      (node (ref "J2") (pin "E10") (pinfunction "E10_E10") (pintype "passive"))
    )
    (net (code "223") (name "unconnected-(J2-PadE12)") (class "Default")
      (node (ref "J2") (pin "E12") (pinfunction "E12_E12") (pintype "passive"))
    )
    (net (code "224") (name "unconnected-(J2-PadE13)") (class "Default")
      (node (ref "J2") (pin "E13") (pinfunction "E13_E13") (pintype "passive"))
    )
    (net (code "225") (name "unconnected-(J2-PadE15)") (class "Default")
      (node (ref "J2") (pin "E15") (pinfunction "E15_E15") (pintype "passive"))
    )
    (net (code "226") (name "unconnected-(J2-PadE16)") (class "Default")
      (node (ref "J2") (pin "E16") (pinfunction "E16_E16") (pintype "passive"))
    )
    (net (code "227") (name "unconnected-(J2-PadE18)") (class "Default")
      (node (ref "J2") (pin "E18") (pinfunction "E18_E18") (pintype "passive"))
    )
    (net (code "228") (name "unconnected-(J2-PadE19)") (class "Default")
      (node (ref "J2") (pin "E19") (pinfunction "E19_E19") (pintype "passive"))
    )
    (net (code "229") (name "unconnected-(J2-PadE21)") (class "Default")
      (node (ref "J2") (pin "E21") (pinfunction "E21_E21") (pintype "passive"))
    )
    (net (code "230") (name "unconnected-(J2-PadE22)") (class "Default")
      (node (ref "J2") (pin "E22") (pinfunction "E22_E22") (pintype "passive"))
    )
    (net (code "231") (name "unconnected-(J2-PadE24)") (class "Default")
      (node (ref "J2") (pin "E24") (pinfunction "E24_E24") (pintype "passive"))
    )
    (net (code "232") (name "unconnected-(J2-PadE25)") (class "Default")
      (node (ref "J2") (pin "E25") (pinfunction "E25_E25") (pintype "passive"))
    )
    (net (code "233") (name "unconnected-(J2-PadE27)") (class "Default")
      (node (ref "J2") (pin "E27") (pinfunction "E27_E27") (pintype "passive"))
    )
    (net (code "234") (name "unconnected-(J2-PadE28)") (class "Default")
      (node (ref "J2") (pin "E28") (pinfunction "E28_E28") (pintype "passive"))
    )
    (net (code "235") (name "unconnected-(J2-PadE30)") (class "Default")
      (node (ref "J2") (pin "E30") (pinfunction "E30_E30") (pintype "passive"))
    )
    (net (code "236") (name "unconnected-(J2-PadE31)") (class "Default")
      (node (ref "J2") (pin "E31") (pinfunction "E31_E31") (pintype "passive"))
    )
    (net (code "237") (name "unconnected-(J2-PadE33)") (class "Default")
      (node (ref "J2") (pin "E33") (pinfunction "E33_E33") (pintype "passive"))
    )
    (net (code "238") (name "unconnected-(J2-PadE34)") (class "Default")
      (node (ref "J2") (pin "E34") (pinfunction "E34_E34") (pintype "passive"))
    )
    (net (code "239") (name "unconnected-(J2-PadE36)") (class "Default")
      (node (ref "J2") (pin "E36") (pinfunction "E36_E36") (pintype "passive"))
    )
    (net (code "240") (name "unconnected-(J2-PadE37)") (class "Default")
      (node (ref "J2") (pin "E37") (pinfunction "E37_E37") (pintype "passive"))
    )
    (net (code "241") (name "unconnected-(J2-PadF1)") (class "Default")
      (node (ref "J2") (pin "F1") (pinfunction "F1_F1") (pintype "passive"))
    )
    (net (code "242") (name "unconnected-(J2-PadF4)") (class "Default")
      (node (ref "J2") (pin "F4") (pinfunction "F4_F4") (pintype "passive"))
    )
    (net (code "243") (name "unconnected-(J2-PadF5)") (class "Default")
      (node (ref "J2") (pin "F5") (pinfunction "F5_F5") (pintype "passive"))
    )
    (net (code "244") (name "unconnected-(J2-PadF7)") (class "Default")
      (node (ref "J2") (pin "F7") (pinfunction "F7_F7") (pintype "passive"))
    )
    (net (code "245") (name "unconnected-(J2-PadF8)") (class "Default")
      (node (ref "J2") (pin "F8") (pinfunction "F8_F8") (pintype "passive"))
    )
    (net (code "246") (name "unconnected-(J2-PadF10)") (class "Default")
      (node (ref "J2") (pin "F10") (pinfunction "F10_F10") (pintype "passive"))
    )
    (net (code "247") (name "unconnected-(J2-PadF11)") (class "Default")
      (node (ref "J2") (pin "F11") (pinfunction "F11_F11") (pintype "passive"))
    )
    (net (code "248") (name "unconnected-(J2-PadF13)") (class "Default")
      (node (ref "J2") (pin "F13") (pinfunction "F13_F13") (pintype "passive"))
    )
    (net (code "249") (name "unconnected-(J2-PadF14)") (class "Default")
      (node (ref "J2") (pin "F14") (pinfunction "F14_F14") (pintype "passive"))
    )
    (net (code "250") (name "unconnected-(J2-PadF16)") (class "Default")
      (node (ref "J2") (pin "F16") (pinfunction "F16_F16") (pintype "passive"))
    )
    (net (code "251") (name "unconnected-(J2-PadF17)") (class "Default")
      (node (ref "J2") (pin "F17") (pinfunction "F17_F17") (pintype "passive"))
    )
    (net (code "252") (name "unconnected-(J2-PadF19)") (class "Default")
      (node (ref "J2") (pin "F19") (pinfunction "F19_F19") (pintype "passive"))
    )
    (net (code "253") (name "unconnected-(J2-PadF20)") (class "Default")
      (node (ref "J2") (pin "F20") (pinfunction "F20_F20") (pintype "passive"))
    )
    (net (code "254") (name "unconnected-(J2-PadF22)") (class "Default")
      (node (ref "J2") (pin "F22") (pinfunction "F22_F22") (pintype "passive"))
    )
    (net (code "255") (name "unconnected-(J2-PadF23)") (class "Default")
      (node (ref "J2") (pin "F23") (pinfunction "F23_F23") (pintype "passive"))
    )
    (net (code "256") (name "unconnected-(J2-PadF25)") (class "Default")
      (node (ref "J2") (pin "F25") (pinfunction "F25_F25") (pintype "passive"))
    )
    (net (code "257") (name "unconnected-(J2-PadF26)") (class "Default")
      (node (ref "J2") (pin "F26") (pinfunction "F26_F26") (pintype "passive"))
    )
    (net (code "258") (name "unconnected-(J2-PadF28)") (class "Default")
      (node (ref "J2") (pin "F28") (pinfunction "F28_F28") (pintype "passive"))
    )
    (net (code "259") (name "unconnected-(J2-PadF29)") (class "Default")
      (node (ref "J2") (pin "F29") (pinfunction "F29_F29") (pintype "passive"))
    )
    (net (code "260") (name "unconnected-(J2-PadF31)") (class "Default")
      (node (ref "J2") (pin "F31") (pinfunction "F31_F31") (pintype "passive"))
    )
    (net (code "261") (name "unconnected-(J2-PadF32)") (class "Default")
      (node (ref "J2") (pin "F32") (pinfunction "F32_F32") (pintype "passive"))
    )
    (net (code "262") (name "unconnected-(J2-PadF34)") (class "Default")
      (node (ref "J2") (pin "F34") (pinfunction "F34_F34") (pintype "passive"))
    )
    (net (code "263") (name "unconnected-(J2-PadF35)") (class "Default")
      (node (ref "J2") (pin "F35") (pinfunction "F35_F35") (pintype "passive"))
    )
    (net (code "264") (name "unconnected-(J2-PadF37)") (class "Default")
      (node (ref "J2") (pin "F37") (pinfunction "F37_F37") (pintype "passive"))
    )
    (net (code "265") (name "unconnected-(J2-PadF38)") (class "Default")
      (node (ref "J2") (pin "F38") (pinfunction "F38_F38") (pintype "passive"))
    )
    (net (code "266") (name "unconnected-(J2-PadH1)") (class "Default")
      (node (ref "J2") (pin "H1") (pinfunction "H1_H1") (pintype "passive"))
    )
    (net (code "267") (name "unconnected-(J2-PadJ2)") (class "Default")
      (node (ref "J2") (pin "J2") (pinfunction "J2_J2") (pintype "passive"))
    )
    (net (code "268") (name "unconnected-(J2-PadJ3)") (class "Default")
      (node (ref "J2") (pin "J3") (pinfunction "J3_J3") (pintype "passive"))
    )
    (net (code "269") (name "unconnected-(J2-PadJ6)") (class "Default")
      (node (ref "J2") (pin "J6") (pinfunction "J6_J6") (pintype "passive"))
    )
    (net (code "270") (name "unconnected-(J2-PadJ7)") (class "Default")
      (node (ref "J2") (pin "J7") (pinfunction "J7_J7") (pintype "passive"))
    )
    (net (code "271") (name "unconnected-(J2-PadJ9)") (class "Default")
      (node (ref "J2") (pin "J9") (pinfunction "J9_J9") (pintype "passive"))
    )
    (net (code "272") (name "unconnected-(J2-PadJ10)") (class "Default")
      (node (ref "J2") (pin "J10") (pinfunction "J10_J10") (pintype "passive"))
    )
    (net (code "273") (name "unconnected-(J2-PadJ12)") (class "Default")
      (node (ref "J2") (pin "J12") (pinfunction "J12_J12") (pintype "passive"))
    )
    (net (code "274") (name "unconnected-(J2-PadJ13)") (class "Default")
      (node (ref "J2") (pin "J13") (pinfunction "J13_J13") (pintype "passive"))
    )
    (net (code "275") (name "unconnected-(J2-PadJ15)") (class "Default")
      (node (ref "J2") (pin "J15") (pinfunction "J15_J15") (pintype "passive"))
    )
    (net (code "276") (name "unconnected-(J2-PadJ16)") (class "Default")
      (node (ref "J2") (pin "J16") (pinfunction "J16_J16") (pintype "passive"))
    )
    (net (code "277") (name "unconnected-(J2-PadJ18)") (class "Default")
      (node (ref "J2") (pin "J18") (pinfunction "J18_J18") (pintype "passive"))
    )
    (net (code "278") (name "unconnected-(J2-PadJ19)") (class "Default")
      (node (ref "J2") (pin "J19") (pinfunction "J19_J19") (pintype "passive"))
    )
    (net (code "279") (name "unconnected-(J2-PadJ21)") (class "Default")
      (node (ref "J2") (pin "J21") (pinfunction "J21_J21") (pintype "passive"))
    )
    (net (code "280") (name "unconnected-(J2-PadJ22)") (class "Default")
      (node (ref "J2") (pin "J22") (pinfunction "J22_J22") (pintype "passive"))
    )
    (net (code "281") (name "unconnected-(J2-PadJ24)") (class "Default")
      (node (ref "J2") (pin "J24") (pinfunction "J24_J24") (pintype "passive"))
    )
    (net (code "282") (name "unconnected-(J2-PadJ25)") (class "Default")
      (node (ref "J2") (pin "J25") (pinfunction "J25_J25") (pintype "passive"))
    )
    (net (code "283") (name "unconnected-(J2-PadJ27)") (class "Default")
      (node (ref "J2") (pin "J27") (pinfunction "J27_J27") (pintype "passive"))
    )
    (net (code "284") (name "unconnected-(J2-PadJ28)") (class "Default")
      (node (ref "J2") (pin "J28") (pinfunction "J28_J28") (pintype "passive"))
    )
    (net (code "285") (name "unconnected-(J2-PadJ30)") (class "Default")
      (node (ref "J2") (pin "J30") (pinfunction "J30_J30") (pintype "passive"))
    )
    (net (code "286") (name "unconnected-(J2-PadJ31)") (class "Default")
      (node (ref "J2") (pin "J31") (pinfunction "J31_J31") (pintype "passive"))
    )
    (net (code "287") (name "unconnected-(J2-PadJ33)") (class "Default")
      (node (ref "J2") (pin "J33") (pinfunction "J33_J33") (pintype "passive"))
    )
    (net (code "288") (name "unconnected-(J2-PadJ34)") (class "Default")
      (node (ref "J2") (pin "J34") (pinfunction "J34_J34") (pintype "passive"))
    )
    (net (code "289") (name "unconnected-(J2-PadJ36)") (class "Default")
      (node (ref "J2") (pin "J36") (pinfunction "J36_J36") (pintype "passive"))
    )
    (net (code "290") (name "unconnected-(J2-PadJ37)") (class "Default")
      (node (ref "J2") (pin "J37") (pinfunction "J37_J37") (pintype "passive"))
    )
    (net (code "291") (name "unconnected-(J2-PadJ39)") (class "Default")
      (node (ref "J2") (pin "J39") (pinfunction "J39_J39") (pintype "passive"))
    )
    (net (code "292") (name "unconnected-(J2-PadK1)") (class "Default")
      (node (ref "J2") (pin "K1") (pinfunction "K1_K1") (pintype "passive"))
    )
    (net (code "293") (name "unconnected-(J2-PadK4)") (class "Default")
      (node (ref "J2") (pin "K4") (pinfunction "K4_K4") (pintype "passive"))
    )
    (net (code "294") (name "unconnected-(J2-PadK5)") (class "Default")
      (node (ref "J2") (pin "K5") (pinfunction "K5_K5") (pintype "passive"))
    )
    (net (code "295") (name "unconnected-(J2-PadK7)") (class "Default")
      (node (ref "J2") (pin "K7") (pinfunction "K7_K7") (pintype "passive"))
    )
    (net (code "296") (name "unconnected-(J2-PadK8)") (class "Default")
      (node (ref "J2") (pin "K8") (pinfunction "K8_K8") (pintype "passive"))
    )
    (net (code "297") (name "unconnected-(J2-PadK10)") (class "Default")
      (node (ref "J2") (pin "K10") (pinfunction "K10_K10") (pintype "passive"))
    )
    (net (code "298") (name "unconnected-(J2-PadK11)") (class "Default")
      (node (ref "J2") (pin "K11") (pinfunction "K11_K11") (pintype "passive"))
    )
    (net (code "299") (name "unconnected-(J2-PadK13)") (class "Default")
      (node (ref "J2") (pin "K13") (pinfunction "K13_K13") (pintype "passive"))
    )
    (net (code "300") (name "unconnected-(J2-PadK14)") (class "Default")
      (node (ref "J2") (pin "K14") (pinfunction "K14_K14") (pintype "passive"))
    )
    (net (code "301") (name "unconnected-(J2-PadK16)") (class "Default")
      (node (ref "J2") (pin "K16") (pinfunction "K16_K16") (pintype "passive"))
    )
    (net (code "302") (name "unconnected-(J2-PadK17)") (class "Default")
      (node (ref "J2") (pin "K17") (pinfunction "K17_K17") (pintype "passive"))
    )
    (net (code "303") (name "unconnected-(J2-PadK19)") (class "Default")
      (node (ref "J2") (pin "K19") (pinfunction "K19_K19") (pintype "passive"))
    )
    (net (code "304") (name "unconnected-(J2-PadK20)") (class "Default")
      (node (ref "J2") (pin "K20") (pinfunction "K20_K20") (pintype "passive"))
    )
    (net (code "305") (name "unconnected-(J2-PadK22)") (class "Default")
      (node (ref "J2") (pin "K22") (pinfunction "K22_K22") (pintype "passive"))
    )
    (net (code "306") (name "unconnected-(J2-PadK23)") (class "Default")
      (node (ref "J2") (pin "K23") (pinfunction "K23_K23") (pintype "passive"))
    )
    (net (code "307") (name "unconnected-(J2-PadK25)") (class "Default")
      (node (ref "J2") (pin "K25") (pinfunction "K25_K25") (pintype "passive"))
    )
    (net (code "308") (name "unconnected-(J2-PadK26)") (class "Default")
      (node (ref "J2") (pin "K26") (pinfunction "K26_K26") (pintype "passive"))
    )
    (net (code "309") (name "unconnected-(J2-PadK28)") (class "Default")
      (node (ref "J2") (pin "K28") (pinfunction "K28_K28") (pintype "passive"))
    )
    (net (code "310") (name "unconnected-(J2-PadK29)") (class "Default")
      (node (ref "J2") (pin "K29") (pinfunction "K29_K29") (pintype "passive"))
    )
    (net (code "311") (name "unconnected-(J2-PadK31)") (class "Default")
      (node (ref "J2") (pin "K31") (pinfunction "K31_K31") (pintype "passive"))
    )
    (net (code "312") (name "unconnected-(J2-PadK32)") (class "Default")
      (node (ref "J2") (pin "K32") (pinfunction "K32_K32") (pintype "passive"))
    )
    (net (code "313") (name "unconnected-(J2-PadK34)") (class "Default")
      (node (ref "J2") (pin "K34") (pinfunction "K34_K34") (pintype "passive"))
    )
    (net (code "314") (name "unconnected-(J2-PadK35)") (class "Default")
      (node (ref "J2") (pin "K35") (pinfunction "K35_K35") (pintype "passive"))
    )
    (net (code "315") (name "unconnected-(J2-PadK37)") (class "Default")
      (node (ref "J2") (pin "K37") (pinfunction "K37_K37") (pintype "passive"))
    )
    (net (code "316") (name "unconnected-(J2-PadK38)") (class "Default")
      (node (ref "J2") (pin "K38") (pinfunction "K38_K38") (pintype "passive"))
    )
    (net (code "317") (name "unconnected-(J2-PadK40)") (class "Default")
      (node (ref "J2") (pin "K40") (pinfunction "K40_K40") (pintype "passive"))
    )
  )
)
